# 4XKanda_1276_NoBME.net
KiCad netlist of a schematic drawn in EAGLE
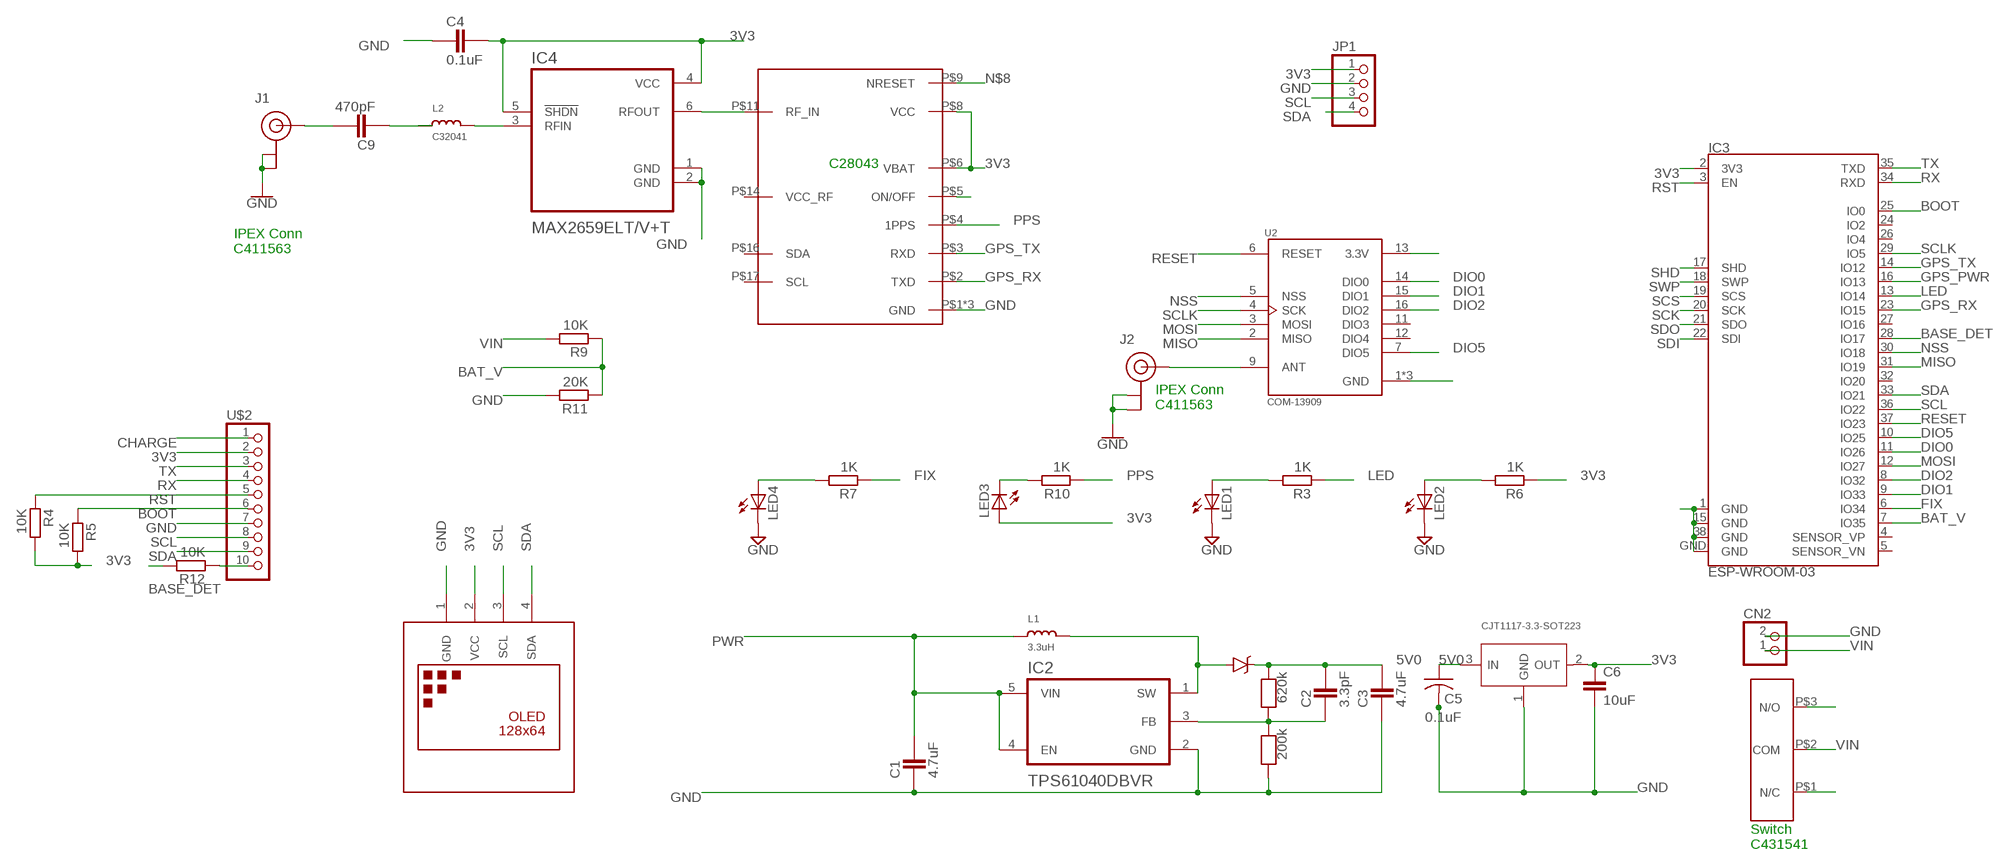
[diagram p0: schematic, sheet 1]
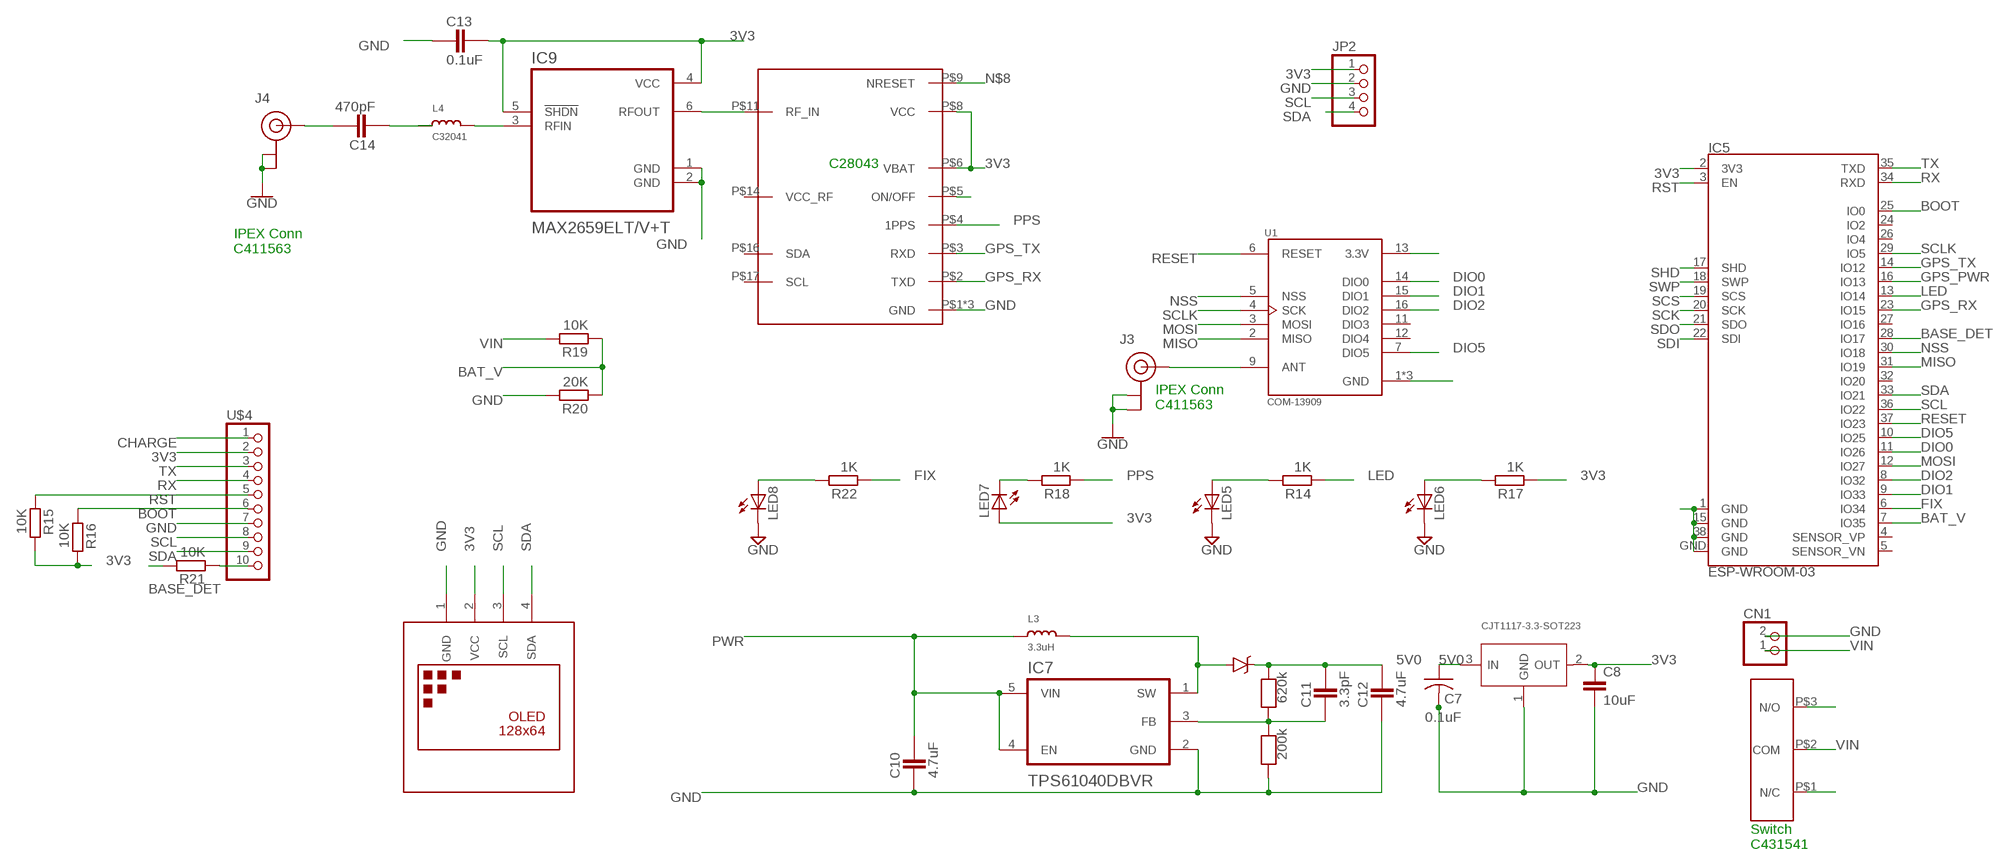
[diagram p1: schematic, sheet 2]
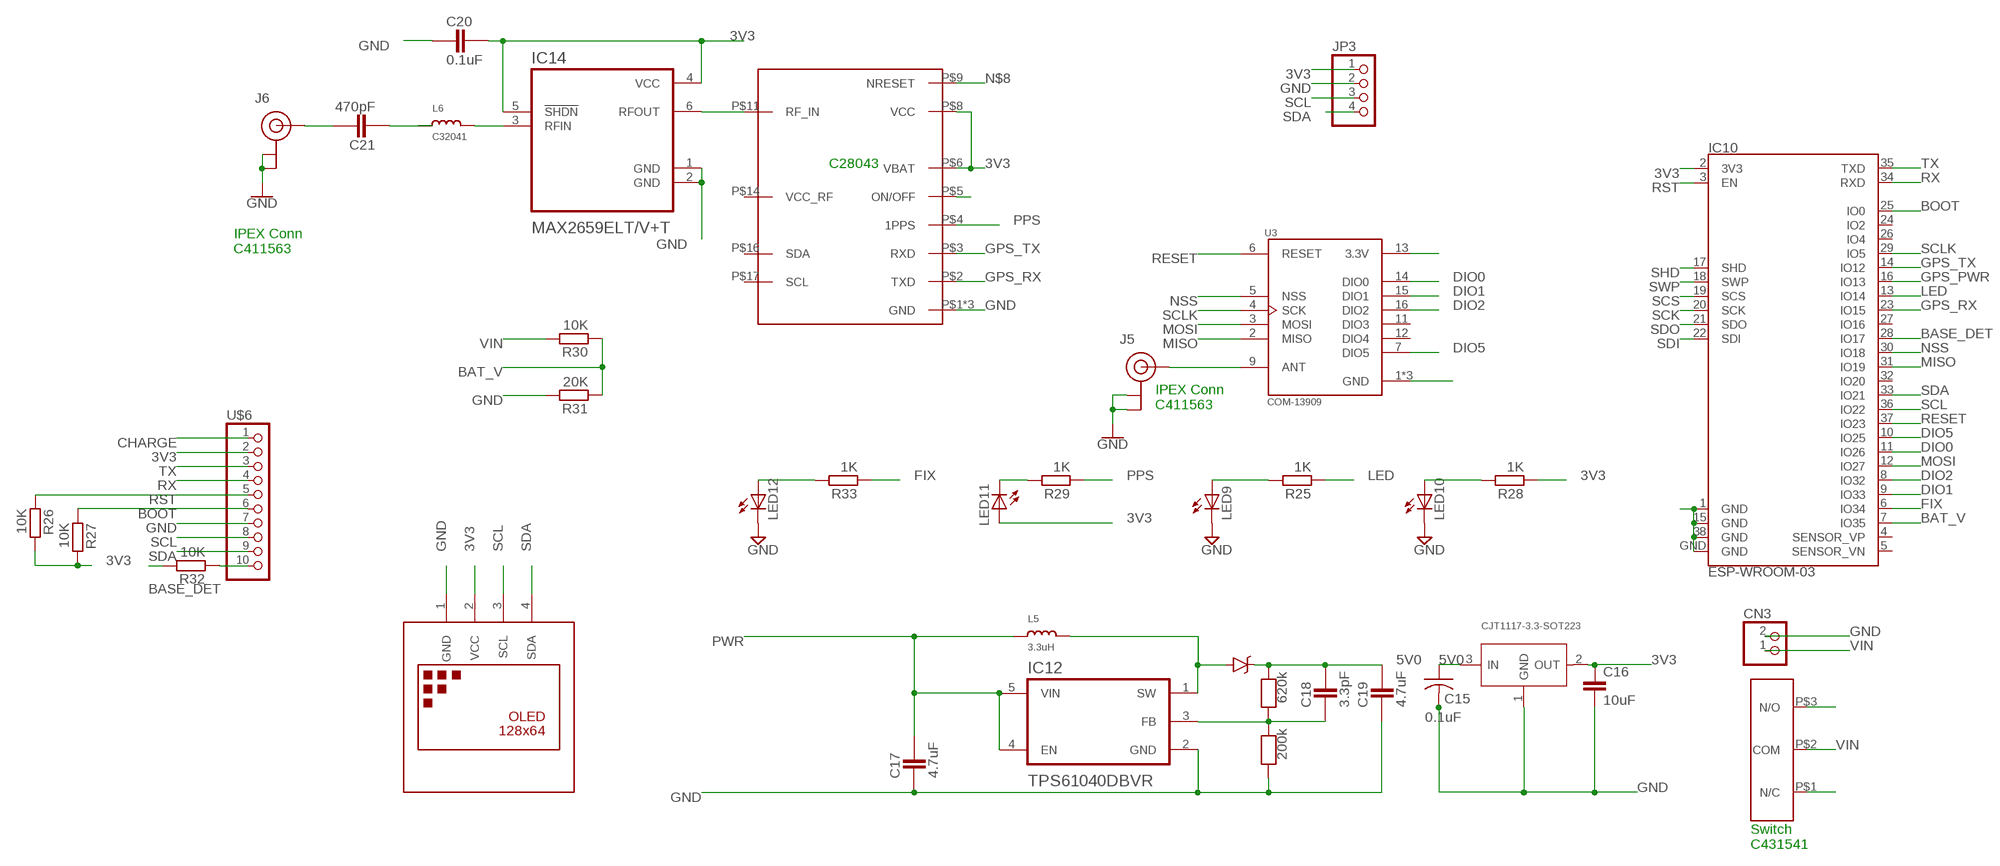
[diagram p2: schematic, sheet 3]
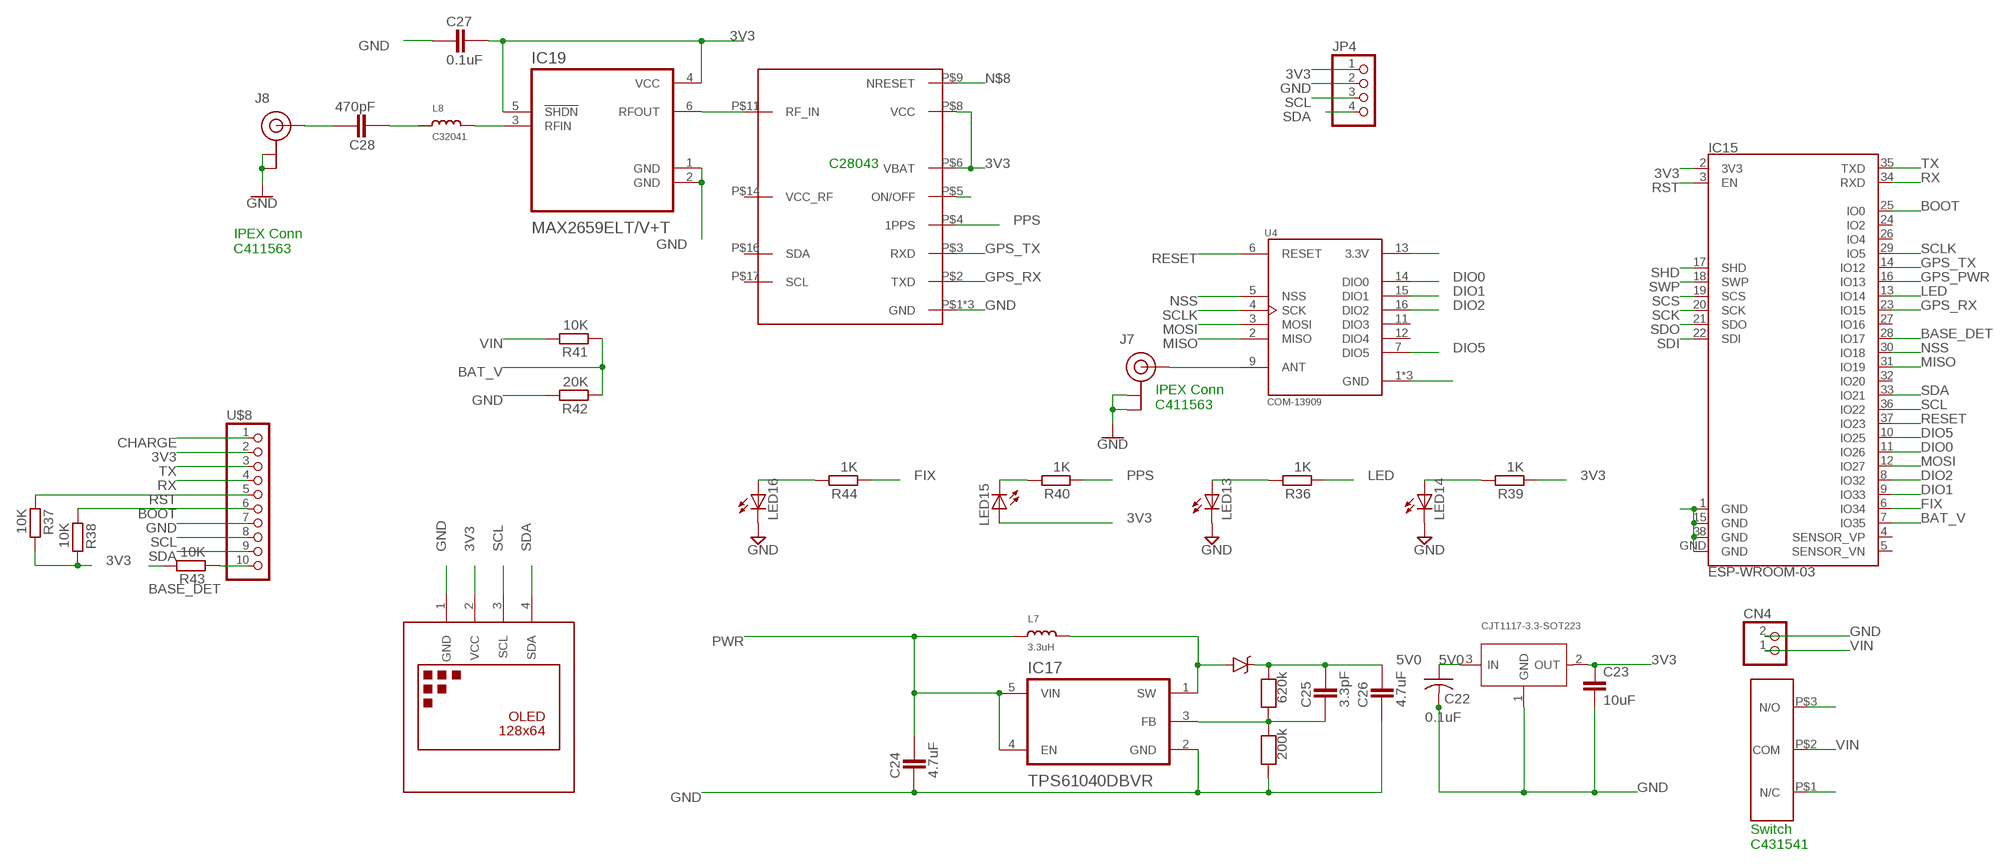
[diagram p3: schematic, sheet 4]

(export (version "E")
  (design (tool "Eeschema 10.0.6"))
  (components
    (comp (ref "C7")
      (value "0.1uF")
      (footprint "eagle-import:C0805")
      (libsource (lib "eagle-import") (part "C-USC0805"))
    )
    (comp (ref "C8")
      (value "10uF")
      (footprint "eagle-import:C0805@1")
      (libsource (lib "eagle-import") (part "C-EUC0805"))
    )
    (comp (ref "C10")
      (value "4.7uF")
      (footprint "eagle-import:CAPC1608X92N")
      (libsource (lib "eagle-import") (part "CAPACITOR_0603"))
    )
    (comp (ref "C11")
      (value "3.3pF")
      (footprint "eagle-import:CAPC1005X60N")
      (libsource (lib "eagle-import") (part "CAPACITOR_0402"))
    )
    (comp (ref "C12")
      (value "4.7uF")
      (footprint "eagle-import:CAPC1608X92N")
      (libsource (lib "eagle-import") (part "CAPACITOR_0603"))
    )
    (comp (ref "C13")
      (value "0.1uF")
      (footprint "eagle-import:CAPC1608X92N")
      (libsource (lib "eagle-import") (part "CAPACITOR_0603"))
    )
    (comp (ref "C14")
      (value "470pF")
      (footprint "eagle-import:CAPC1608X92N")
      (libsource (lib "eagle-import") (part "CAPACITOR_0603"))
    )
    (comp (ref "CN1")
      (value "JST_2PIN-THM")
      (footprint "eagle-import:JST-PH-2-THM")
      (libsource (lib "eagle-import") (part "JST_2PIN-THM"))
    )
    (comp (ref "D2")
      (value "BA340A")
      (footprint "eagle-import:SMA-DIODE")
      (libsource (lib "eagle-import") (part "B340A"))
    )
    (comp (ref "IC5")
      (value "ESP-WROOM-03")
      (footprint "eagle-import:ESP-WROOM-03")
      (libsource (lib "eagle-import") (part "ESP-WROOM-03"))
    )
    (comp (ref "IC6")
      (value "CJT1117-3.3-SOT223")
      (footprint "eagle-import:SOT-223")
      (fields (field (name "MPN") "CJT1117-3.3"))
      (libsource (lib "eagle-import") (part "PMIC-CJT1117-3.3(SOT223)"))
    )
    (comp (ref "IC7")
      (value "TPS61040DBVR")
      (footprint "eagle-import:SOT95P280X145-5N")
      (fields (field (name "MF") "Texas Instruments"))
      (libsource (lib "eagle-import") (part "TPS61040DBVR"))
    )
    (comp (ref "IC8")
      (value "ATGM336H")
      (footprint "eagle-import:ATGM336H")
      (libsource (lib "eagle-import") (part "ATGM336H"))
    )
    (comp (ref "IC9")
      (value "MAX2659ELT/V+T")
      (footprint "eagle-import:SON50P150X100X80-6N")
      (fields (field (name "MF") "Maxim Integrated") (field (name "MP") "MAX2659ELT/V+"))
      (libsource (lib "eagle-import") (part "MAX2659ELT/V+T"))
    )
    (comp (ref "J3")
      (value "U.FL")
      (footprint "eagle-import:U.FL")
      (libsource (lib "eagle-import") (part "U.FL"))
    )
    (comp (ref "J4")
      (value "U.FL")
      (footprint "eagle-import:U.FL")
      (libsource (lib "eagle-import") (part "U.FL"))
    )
    (comp (ref "JP2")
      (value "HEADER-1X4ROUND")
      (footprint "eagle-import:1X04_ROUND")
      (libsource (lib "eagle-import") (part "HEADER-1X4ROUND"))
    )
    (comp (ref "L3")
      (value "3.3uH")
      (footprint "eagle-import:INDUCTOR_5X5MM_NR5040_NOTHERMALS")
      (libsource (lib "eagle-import") (part "INDUCTORNR5040"))
    )
    (comp (ref "L4")
      (value "C32041")
      (footprint "eagle-import:_0402")
      (libsource (lib "eagle-import") (part "INDUCTOR_0402"))
    )
    (comp (ref "LED5")
      (value "LEDSML0805")
      (footprint "eagle-import:SML0805")
      (libsource (lib "eagle-import") (part "LEDSML0805"))
    )
    (comp (ref "LED6")
      (value "LEDSML0805")
      (footprint "eagle-import:SML0805")
      (libsource (lib "eagle-import") (part "LEDSML0805"))
    )
    (comp (ref "LED7")
      (value "LEDSML0805")
      (footprint "eagle-import:SML0805")
      (libsource (lib "eagle-import") (part "LEDSML0805"))
    )
    (comp (ref "LED8")
      (value "LEDSML0805")
      (footprint "eagle-import:SML0805")
      (libsource (lib "eagle-import") (part "LEDSML0805"))
    )
    (comp (ref "R8")
      (value "620k")
      (footprint "eagle-import:0603")
      (libsource (lib "eagle-import") (part "RESISTOR0603"))
    )
    (comp (ref "R13")
      (value "200k")
      (footprint "eagle-import:0603")
      (libsource (lib "eagle-import") (part "RESISTOR0603"))
    )
    (comp (ref "R14")
      (value "1K")
      (footprint "eagle-import:RESC1608X55N")
      (libsource (lib "eagle-import") (part "RESISTOR_0603"))
    )
    (comp (ref "R15")
      (value "10K")
      (footprint "eagle-import:RESC1608X55N")
      (libsource (lib "eagle-import") (part "RESISTOR_0603"))
    )
    (comp (ref "R16")
      (value "10K")
      (footprint "eagle-import:RESC1608X55N")
      (libsource (lib "eagle-import") (part "RESISTOR_0603"))
    )
    (comp (ref "R17")
      (value "1K")
      (footprint "eagle-import:RESC2012X70N")
      (libsource (lib "eagle-import") (part "RESISTOR_0805"))
    )
    (comp (ref "R18")
      (value "1K")
      (footprint "eagle-import:RESC1608X55N")
      (libsource (lib "eagle-import") (part "RESISTOR_0603"))
    )
    (comp (ref "R19")
      (value "10K")
      (footprint "eagle-import:RESC1608X55N")
      (libsource (lib "eagle-import") (part "RESISTOR_0603"))
    )
    (comp (ref "R20")
      (value "20K")
      (footprint "eagle-import:RESC1608X55N")
      (libsource (lib "eagle-import") (part "RESISTOR_0603"))
    )
    (comp (ref "R21")
      (value "10K")
      (footprint "eagle-import:RESC1608X55N")
      (libsource (lib "eagle-import") (part "RESISTOR_0603"))
    )
    (comp (ref "R22")
      (value "1K")
      (footprint "eagle-import:RESC1608X55N")
      (libsource (lib "eagle-import") (part "RESISTOR_0603"))
    )
    (comp (ref "S2")
      (value "SMD-SWITCH")
      (footprint "eagle-import:SMD-SWITCH")
      (libsource (lib "eagle-import") (part "SMD-SWITCH"))
    )
    (comp (ref "U$3")
      (value "DISPLAY-OLED-128X64-I2C")
      (footprint "eagle-import:DISPLAY-OLED-128X64-I2C")
      (libsource (lib "eagle-import") (part "DISPLAY-OLED-128X64-I2C"))
    )
    (comp (ref "U$4")
      (value "HEADER-1X10ROUND")
      (footprint "eagle-import:1X10_ROUND")
      (libsource (lib "eagle-import") (part "HEADER-1X10ROUND"))
    )
    (comp (ref "U1")
      (value "COM-13909")
      (footprint "eagle-import:MOD_COM-13909")
      (fields (field (name "MF") "HOPERF") (field (name "MP") "RFM69HCW-315S2"))
      (libsource (lib "eagle-import") (part "COM-13909"))
    )
    (comp (ref "C15")
      (value "0.1uF")
      (footprint "eagle-import:C0805")
      (libsource (lib "eagle-import") (part "C-USC0805"))
    )
    (comp (ref "C16")
      (value "10uF")
      (footprint "eagle-import:C0805@1")
      (libsource (lib "eagle-import") (part "C-EUC0805"))
    )
    (comp (ref "C17")
      (value "4.7uF")
      (footprint "eagle-import:CAPC1608X92N")
      (libsource (lib "eagle-import") (part "CAPACITOR_0603"))
    )
    (comp (ref "C18")
      (value "3.3pF")
      (footprint "eagle-import:CAPC1005X60N")
      (libsource (lib "eagle-import") (part "CAPACITOR_0402"))
    )
    (comp (ref "C19")
      (value "4.7uF")
      (footprint "eagle-import:CAPC1608X92N")
      (libsource (lib "eagle-import") (part "CAPACITOR_0603"))
    )
    (comp (ref "C20")
      (value "0.1uF")
      (footprint "eagle-import:CAPC1608X92N")
      (libsource (lib "eagle-import") (part "CAPACITOR_0603"))
    )
    (comp (ref "C21")
      (value "470pF")
      (footprint "eagle-import:CAPC1608X92N")
      (libsource (lib "eagle-import") (part "CAPACITOR_0603"))
    )
    (comp (ref "CN3")
      (value "JST_2PIN-THM")
      (footprint "eagle-import:JST-PH-2-THM")
      (libsource (lib "eagle-import") (part "JST_2PIN-THM"))
    )
    (comp (ref "D3")
      (value "BA340A")
      (footprint "eagle-import:SMA-DIODE")
      (libsource (lib "eagle-import") (part "B340A"))
    )
    (comp (ref "IC10")
      (value "ESP-WROOM-03")
      (footprint "eagle-import:ESP-WROOM-03")
      (libsource (lib "eagle-import") (part "ESP-WROOM-03"))
    )
    (comp (ref "IC11")
      (value "CJT1117-3.3-SOT223")
      (footprint "eagle-import:SOT-223")
      (fields (field (name "MPN") "CJT1117-3.3"))
      (libsource (lib "eagle-import") (part "PMIC-CJT1117-3.3(SOT223)"))
    )
    (comp (ref "IC12")
      (value "TPS61040DBVR")
      (footprint "eagle-import:SOT95P280X145-5N")
      (fields (field (name "MF") "Texas Instruments"))
      (libsource (lib "eagle-import") (part "TPS61040DBVR"))
    )
    (comp (ref "IC13")
      (value "ATGM336H")
      (footprint "eagle-import:ATGM336H")
      (libsource (lib "eagle-import") (part "ATGM336H"))
    )
    (comp (ref "IC14")
      (value "MAX2659ELT/V+T")
      (footprint "eagle-import:SON50P150X100X80-6N")
      (fields (field (name "MF") "Maxim Integrated") (field (name "MP") "MAX2659ELT/V+"))
      (libsource (lib "eagle-import") (part "MAX2659ELT/V+T"))
    )
    (comp (ref "J5")
      (value "U.FL")
      (footprint "eagle-import:U.FL")
      (libsource (lib "eagle-import") (part "U.FL"))
    )
    (comp (ref "J6")
      (value "U.FL")
      (footprint "eagle-import:U.FL")
      (libsource (lib "eagle-import") (part "U.FL"))
    )
    (comp (ref "JP3")
      (value "HEADER-1X4ROUND")
      (footprint "eagle-import:1X04_ROUND")
      (libsource (lib "eagle-import") (part "HEADER-1X4ROUND"))
    )
    (comp (ref "L5")
      (value "3.3uH")
      (footprint "eagle-import:INDUCTOR_5X5MM_NR5040_NOTHERMALS")
      (libsource (lib "eagle-import") (part "INDUCTORNR5040"))
    )
    (comp (ref "L6")
      (value "C32041")
      (footprint "eagle-import:_0402")
      (libsource (lib "eagle-import") (part "INDUCTOR_0402"))
    )
    (comp (ref "LED9")
      (value "LEDSML0805")
      (footprint "eagle-import:SML0805")
      (libsource (lib "eagle-import") (part "LEDSML0805"))
    )
    (comp (ref "LED10")
      (value "LEDSML0805")
      (footprint "eagle-import:SML0805")
      (libsource (lib "eagle-import") (part "LEDSML0805"))
    )
    (comp (ref "LED11")
      (value "LEDSML0805")
      (footprint "eagle-import:SML0805")
      (libsource (lib "eagle-import") (part "LEDSML0805"))
    )
    (comp (ref "LED12")
      (value "LEDSML0805")
      (footprint "eagle-import:SML0805")
      (libsource (lib "eagle-import") (part "LEDSML0805"))
    )
    (comp (ref "R23")
      (value "620k")
      (footprint "eagle-import:0603")
      (libsource (lib "eagle-import") (part "RESISTOR0603"))
    )
    (comp (ref "R24")
      (value "200k")
      (footprint "eagle-import:0603")
      (libsource (lib "eagle-import") (part "RESISTOR0603"))
    )
    (comp (ref "R25")
      (value "1K")
      (footprint "eagle-import:RESC1608X55N")
      (libsource (lib "eagle-import") (part "RESISTOR_0603"))
    )
    (comp (ref "R26")
      (value "10K")
      (footprint "eagle-import:RESC1608X55N")
      (libsource (lib "eagle-import") (part "RESISTOR_0603"))
    )
    (comp (ref "R27")
      (value "10K")
      (footprint "eagle-import:RESC1608X55N")
      (libsource (lib "eagle-import") (part "RESISTOR_0603"))
    )
    (comp (ref "R28")
      (value "1K")
      (footprint "eagle-import:RESC2012X70N")
      (libsource (lib "eagle-import") (part "RESISTOR_0805"))
    )
    (comp (ref "R29")
      (value "1K")
      (footprint "eagle-import:RESC1608X55N")
      (libsource (lib "eagle-import") (part "RESISTOR_0603"))
    )
    (comp (ref "R30")
      (value "10K")
      (footprint "eagle-import:RESC1608X55N")
      (libsource (lib "eagle-import") (part "RESISTOR_0603"))
    )
    (comp (ref "R31")
      (value "20K")
      (footprint "eagle-import:RESC1608X55N")
      (libsource (lib "eagle-import") (part "RESISTOR_0603"))
    )
    (comp (ref "R32")
      (value "10K")
      (footprint "eagle-import:RESC1608X55N")
      (libsource (lib "eagle-import") (part "RESISTOR_0603"))
    )
    (comp (ref "R33")
      (value "1K")
      (footprint "eagle-import:RESC1608X55N")
      (libsource (lib "eagle-import") (part "RESISTOR_0603"))
    )
    (comp (ref "S3")
      (value "SMD-SWITCH")
      (footprint "eagle-import:SMD-SWITCH")
      (libsource (lib "eagle-import") (part "SMD-SWITCH"))
    )
    (comp (ref "U$5")
      (value "DISPLAY-OLED-128X64-I2C")
      (footprint "eagle-import:DISPLAY-OLED-128X64-I2C")
      (libsource (lib "eagle-import") (part "DISPLAY-OLED-128X64-I2C"))
    )
    (comp (ref "U$6")
      (value "HEADER-1X10ROUND")
      (footprint "eagle-import:1X10_ROUND")
      (libsource (lib "eagle-import") (part "HEADER-1X10ROUND"))
    )
    (comp (ref "U3")
      (value "COM-13909")
      (footprint "eagle-import:MOD_COM-13909")
      (fields (field (name "MF") "HOPERF") (field (name "MP") "RFM69HCW-315S2"))
      (libsource (lib "eagle-import") (part "COM-13909"))
    )
    (comp (ref "C22")
      (value "0.1uF")
      (footprint "eagle-import:C0805")
      (libsource (lib "eagle-import") (part "C-USC0805"))
    )
    (comp (ref "C23")
      (value "10uF")
      (footprint "eagle-import:C0805@1")
      (libsource (lib "eagle-import") (part "C-EUC0805"))
    )
    (comp (ref "C24")
      (value "4.7uF")
      (footprint "eagle-import:CAPC1608X92N")
      (libsource (lib "eagle-import") (part "CAPACITOR_0603"))
    )
    (comp (ref "C25")
      (value "3.3pF")
      (footprint "eagle-import:CAPC1005X60N")
      (libsource (lib "eagle-import") (part "CAPACITOR_0402"))
    )
    (comp (ref "C26")
      (value "4.7uF")
      (footprint "eagle-import:CAPC1608X92N")
      (libsource (lib "eagle-import") (part "CAPACITOR_0603"))
    )
    (comp (ref "C27")
      (value "0.1uF")
      (footprint "eagle-import:CAPC1608X92N")
      (libsource (lib "eagle-import") (part "CAPACITOR_0603"))
    )
    (comp (ref "C28")
      (value "470pF")
      (footprint "eagle-import:CAPC1608X92N")
      (libsource (lib "eagle-import") (part "CAPACITOR_0603"))
    )
    (comp (ref "CN4")
      (value "JST_2PIN-THM")
      (footprint "eagle-import:JST-PH-2-THM")
      (libsource (lib "eagle-import") (part "JST_2PIN-THM"))
    )
    (comp (ref "D4")
      (value "BA340A")
      (footprint "eagle-import:SMA-DIODE")
      (libsource (lib "eagle-import") (part "B340A"))
    )
    (comp (ref "IC15")
      (value "ESP-WROOM-03")
      (footprint "eagle-import:ESP-WROOM-03")
      (libsource (lib "eagle-import") (part "ESP-WROOM-03"))
    )
    (comp (ref "IC16")
      (value "CJT1117-3.3-SOT223")
      (footprint "eagle-import:SOT-223")
      (fields (field (name "MPN") "CJT1117-3.3"))
      (libsource (lib "eagle-import") (part "PMIC-CJT1117-3.3(SOT223)"))
    )
    (comp (ref "IC17")
      (value "TPS61040DBVR")
      (footprint "eagle-import:SOT95P280X145-5N")
      (fields (field (name "MF") "Texas Instruments"))
      (libsource (lib "eagle-import") (part "TPS61040DBVR"))
    )
    (comp (ref "IC18")
      (value "ATGM336H")
      (footprint "eagle-import:ATGM336H")
      (libsource (lib "eagle-import") (part "ATGM336H"))
    )
    (comp (ref "IC19")
      (value "MAX2659ELT/V+T")
      (footprint "eagle-import:SON50P150X100X80-6N")
      (fields (field (name "MF") "Maxim Integrated") (field (name "MP") "MAX2659ELT/V+"))
      (libsource (lib "eagle-import") (part "MAX2659ELT/V+T"))
    )
    (comp (ref "J7")
      (value "U.FL")
      (footprint "eagle-import:U.FL")
      (libsource (lib "eagle-import") (part "U.FL"))
    )
    (comp (ref "J8")
      (value "U.FL")
      (footprint "eagle-import:U.FL")
      (libsource (lib "eagle-import") (part "U.FL"))
    )
    (comp (ref "JP4")
      (value "HEADER-1X4ROUND")
      (footprint "eagle-import:1X04_ROUND")
      (libsource (lib "eagle-import") (part "HEADER-1X4ROUND"))
    )
    (comp (ref "L7")
      (value "3.3uH")
      (footprint "eagle-import:INDUCTOR_5X5MM_NR5040_NOTHERMALS")
      (libsource (lib "eagle-import") (part "INDUCTORNR5040"))
    )
    (comp (ref "L8")
      (value "C32041")
      (footprint "eagle-import:_0402")
      (libsource (lib "eagle-import") (part "INDUCTOR_0402"))
    )
    (comp (ref "LED13")
      (value "LEDSML0805")
      (footprint "eagle-import:SML0805")
      (libsource (lib "eagle-import") (part "LEDSML0805"))
    )
    (comp (ref "LED14")
      (value "LEDSML0805")
      (footprint "eagle-import:SML0805")
      (libsource (lib "eagle-import") (part "LEDSML0805"))
    )
    (comp (ref "LED15")
      (value "LEDSML0805")
      (footprint "eagle-import:SML0805")
      (libsource (lib "eagle-import") (part "LEDSML0805"))
    )
    (comp (ref "LED16")
      (value "LEDSML0805")
      (footprint "eagle-import:SML0805")
      (libsource (lib "eagle-import") (part "LEDSML0805"))
    )
    (comp (ref "R34")
      (value "620k")
      (footprint "eagle-import:0603")
      (libsource (lib "eagle-import") (part "RESISTOR0603"))
    )
    (comp (ref "R35")
      (value "200k")
      (footprint "eagle-import:0603")
      (libsource (lib "eagle-import") (part "RESISTOR0603"))
    )
    (comp (ref "R36")
      (value "1K")
      (footprint "eagle-import:RESC1608X55N")
      (libsource (lib "eagle-import") (part "RESISTOR_0603"))
    )
    (comp (ref "R37")
      (value "10K")
      (footprint "eagle-import:RESC1608X55N")
      (libsource (lib "eagle-import") (part "RESISTOR_0603"))
    )
    (comp (ref "R38")
      (value "10K")
      (footprint "eagle-import:RESC1608X55N")
      (libsource (lib "eagle-import") (part "RESISTOR_0603"))
    )
    (comp (ref "R39")
      (value "1K")
      (footprint "eagle-import:RESC2012X70N")
      (libsource (lib "eagle-import") (part "RESISTOR_0805"))
    )
    (comp (ref "R40")
      (value "1K")
      (footprint "eagle-import:RESC1608X55N")
      (libsource (lib "eagle-import") (part "RESISTOR_0603"))
    )
    (comp (ref "R41")
      (value "10K")
      (footprint "eagle-import:RESC1608X55N")
      (libsource (lib "eagle-import") (part "RESISTOR_0603"))
    )
    (comp (ref "R42")
      (value "20K")
      (footprint "eagle-import:RESC1608X55N")
      (libsource (lib "eagle-import") (part "RESISTOR_0603"))
    )
    (comp (ref "R43")
      (value "10K")
      (footprint "eagle-import:RESC1608X55N")
      (libsource (lib "eagle-import") (part "RESISTOR_0603"))
    )
    (comp (ref "R44")
      (value "1K")
      (footprint "eagle-import:RESC1608X55N")
      (libsource (lib "eagle-import") (part "RESISTOR_0603"))
    )
    (comp (ref "S4")
      (value "SMD-SWITCH")
      (footprint "eagle-import:SMD-SWITCH")
      (libsource (lib "eagle-import") (part "SMD-SWITCH"))
    )
    (comp (ref "U$7")
      (value "DISPLAY-OLED-128X64-I2C")
      (footprint "eagle-import:DISPLAY-OLED-128X64-I2C")
      (libsource (lib "eagle-import") (part "DISPLAY-OLED-128X64-I2C"))
    )
    (comp (ref "U$8")
      (value "HEADER-1X10ROUND")
      (footprint "eagle-import:1X10_ROUND")
      (libsource (lib "eagle-import") (part "HEADER-1X10ROUND"))
    )
    (comp (ref "U4")
      (value "COM-13909")
      (footprint "eagle-import:MOD_COM-13909")
      (fields (field (name "MF") "HOPERF") (field (name "MP") "RFM69HCW-315S2"))
      (libsource (lib "eagle-import") (part "COM-13909"))
    )
    (comp (ref "C1")
      (value "4.7uF")
      (footprint "eagle-import:CAPC1608X92N")
      (libsource (lib "eagle-import") (part "CAPACITOR_0603"))
    )
    (comp (ref "C2")
      (value "3.3pF")
      (footprint "eagle-import:CAPC1005X60N")
      (libsource (lib "eagle-import") (part "CAPACITOR_0402"))
    )
    (comp (ref "C3")
      (value "4.7uF")
      (footprint "eagle-import:CAPC1608X92N")
      (libsource (lib "eagle-import") (part "CAPACITOR_0603"))
    )
    (comp (ref "C4")
      (value "0.1uF")
      (footprint "eagle-import:CAPC1608X92N")
      (libsource (lib "eagle-import") (part "CAPACITOR_0603"))
    )
    (comp (ref "C5")
      (value "0.1uF")
      (footprint "eagle-import:C0805")
      (libsource (lib "eagle-import") (part "C-USC0805"))
    )
    (comp (ref "C6")
      (value "10uF")
      (footprint "eagle-import:C0805@1")
      (libsource (lib "eagle-import") (part "C-EUC0805"))
    )
    (comp (ref "C9")
      (value "470pF")
      (footprint "eagle-import:CAPC1608X92N")
      (libsource (lib "eagle-import") (part "CAPACITOR_0603"))
    )
    (comp (ref "CN2")
      (value "JST_2PIN-THM")
      (footprint "eagle-import:JST-PH-2-THM")
      (libsource (lib "eagle-import") (part "JST_2PIN-THM"))
    )
    (comp (ref "D1")
      (value "BA340A")
      (footprint "eagle-import:SMA-DIODE")
      (libsource (lib "eagle-import") (part "B340A"))
    )
    (comp (ref "IC1")
      (value "CJT1117-3.3-SOT223")
      (footprint "eagle-import:SOT-223")
      (fields (field (name "MPN") "CJT1117-3.3"))
      (libsource (lib "eagle-import") (part "PMIC-CJT1117-3.3(SOT223)"))
    )
    (comp (ref "IC2")
      (value "TPS61040DBVR")
      (footprint "eagle-import:SOT95P280X145-5N")
      (fields (field (name "MF") "Texas Instruments"))
      (libsource (lib "eagle-import") (part "TPS61040DBVR"))
    )
    (comp (ref "IC3")
      (value "ESP-WROOM-03")
      (footprint "eagle-import:ESP-WROOM-03")
      (libsource (lib "eagle-import") (part "ESP-WROOM-03"))
    )
    (comp (ref "IC4")
      (value "MAX2659ELT/V+T")
      (footprint "eagle-import:SON50P150X100X80-6N")
      (fields (field (name "MF") "Maxim Integrated") (field (name "MP") "MAX2659ELT/V+"))
      (libsource (lib "eagle-import") (part "MAX2659ELT/V+T"))
    )
    (comp (ref "IC54")
      (value "ATGM336H")
      (footprint "eagle-import:ATGM336H")
      (libsource (lib "eagle-import") (part "ATGM336H"))
    )
    (comp (ref "J1")
      (value "U.FL")
      (footprint "eagle-import:U.FL")
      (libsource (lib "eagle-import") (part "U.FL"))
    )
    (comp (ref "J2")
      (value "U.FL")
      (footprint "eagle-import:U.FL")
      (libsource (lib "eagle-import") (part "U.FL"))
    )
    (comp (ref "JP1")
      (value "HEADER-1X4ROUND")
      (footprint "eagle-import:1X04_ROUND")
      (libsource (lib "eagle-import") (part "HEADER-1X4ROUND"))
    )
    (comp (ref "L1")
      (value "3.3uH")
      (footprint "eagle-import:INDUCTOR_5X5MM_NR5040_NOTHERMALS")
      (libsource (lib "eagle-import") (part "INDUCTORNR5040"))
    )
    (comp (ref "L2")
      (value "C32041")
      (footprint "eagle-import:_0402")
      (libsource (lib "eagle-import") (part "INDUCTOR_0402"))
    )
    (comp (ref "LED1")
      (value "LEDSML0805")
      (footprint "eagle-import:SML0805")
      (libsource (lib "eagle-import") (part "LEDSML0805"))
    )
    (comp (ref "LED2")
      (value "LEDSML0805")
      (footprint "eagle-import:SML0805")
      (libsource (lib "eagle-import") (part "LEDSML0805"))
    )
    (comp (ref "LED3")
      (value "LEDSML0805")
      (footprint "eagle-import:SML0805")
      (libsource (lib "eagle-import") (part "LEDSML0805"))
    )
    (comp (ref "LED4")
      (value "LEDSML0805")
      (footprint "eagle-import:SML0805")
      (libsource (lib "eagle-import") (part "LEDSML0805"))
    )
    (comp (ref "R1")
      (value "620k")
      (footprint "eagle-import:0603")
      (libsource (lib "eagle-import") (part "RESISTOR0603"))
    )
    (comp (ref "R2")
      (value "200k")
      (footprint "eagle-import:0603")
      (libsource (lib "eagle-import") (part "RESISTOR0603"))
    )
    (comp (ref "R3")
      (value "1K")
      (footprint "eagle-import:RESC1608X55N")
      (libsource (lib "eagle-import") (part "RESISTOR_0603"))
    )
    (comp (ref "R4")
      (value "10K")
      (footprint "eagle-import:RESC1608X55N")
      (libsource (lib "eagle-import") (part "RESISTOR_0603"))
    )
    (comp (ref "R5")
      (value "10K")
      (footprint "eagle-import:RESC1608X55N")
      (libsource (lib "eagle-import") (part "RESISTOR_0603"))
    )
    (comp (ref "R6")
      (value "1K")
      (footprint "eagle-import:RESC2012X70N")
      (libsource (lib "eagle-import") (part "RESISTOR_0805"))
    )
    (comp (ref "R7")
      (value "1K")
      (footprint "eagle-import:RESC1608X55N")
      (libsource (lib "eagle-import") (part "RESISTOR_0603"))
    )
    (comp (ref "R9")
      (value "10K")
      (footprint "eagle-import:RESC1608X55N")
      (libsource (lib "eagle-import") (part "RESISTOR_0603"))
    )
    (comp (ref "R10")
      (value "1K")
      (footprint "eagle-import:RESC1608X55N")
      (libsource (lib "eagle-import") (part "RESISTOR_0603"))
    )
    (comp (ref "R11")
      (value "20K")
      (footprint "eagle-import:RESC1608X55N")
      (libsource (lib "eagle-import") (part "RESISTOR_0603"))
    )
    (comp (ref "R12")
      (value "10K")
      (footprint "eagle-import:RESC1608X55N")
      (libsource (lib "eagle-import") (part "RESISTOR_0603"))
    )
    (comp (ref "S1")
      (value "SMD-SWITCH")
      (footprint "eagle-import:SMD-SWITCH")
      (libsource (lib "eagle-import") (part "SMD-SWITCH"))
    )
    (comp (ref "U$1")
      (value "DISPLAY-OLED-128X64-I2C")
      (footprint "eagle-import:DISPLAY-OLED-128X64-I2C")
      (libsource (lib "eagle-import") (part "DISPLAY-OLED-128X64-I2C"))
    )
    (comp (ref "U$2")
      (value "HEADER-1X10ROUND")
      (footprint "eagle-import:1X10_ROUND")
      (libsource (lib "eagle-import") (part "HEADER-1X10ROUND"))
    )
    (comp (ref "U2")
      (value "COM-13909")
      (footprint "eagle-import:MOD_COM-13909")
      (fields (field (name "MF") "HOPERF") (field (name "MP") "RFM69HCW-315S2"))
      (libsource (lib "eagle-import") (part "COM-13909"))
    )
  )
  (nets
    (net (code "1") (name "3V3") (class "Default")
      (node (ref "C13") (pin "2") (pinfunction "2_2") (pintype "passive"))
      (node (ref "C16") (pin "1") (pinfunction "1_1") (pintype "passive"))
      (node (ref "C20") (pin "2") (pinfunction "2_2") (pintype "passive"))
      (node (ref "C23") (pin "1") (pinfunction "1_1") (pintype "passive"))
      (node (ref "C27") (pin "2") (pinfunction "2_2") (pintype "passive"))
      (node (ref "C4") (pin "2") (pinfunction "2_2") (pintype "passive"))
      (node (ref "C6") (pin "1") (pinfunction "1_1") (pintype "passive"))
      (node (ref "C8") (pin "1") (pinfunction "1_1") (pintype "passive"))
      (node (ref "IC1") (pin "2") (pinfunction "OUT_2") (pintype "bidirectional"))
      (node (ref "IC10") (pin "2") (pinfunction "3V3_2") (pintype "bidirectional"))
      (node (ref "IC11") (pin "2") (pinfunction "OUT_2") (pintype "bidirectional"))
      (node (ref "IC13") (pin "P$6") (pinfunction "VBAT_P$6") (pintype "bidirectional"))
      (node (ref "IC13") (pin "P$8") (pinfunction "VCC_P$8") (pintype "bidirectional"))
      (node (ref "IC14") (pin "4") (pinfunction "VCC_4") (pintype "power_in"))
      (node (ref "IC14") (pin "5") (pinfunction "~{SHDN}_5") (pintype "input"))
      (node (ref "IC15") (pin "2") (pinfunction "3V3_2") (pintype "bidirectional"))
      (node (ref "IC16") (pin "2") (pinfunction "OUT_2") (pintype "bidirectional"))
      (node (ref "IC18") (pin "P$6") (pinfunction "VBAT_P$6") (pintype "bidirectional"))
      (node (ref "IC18") (pin "P$8") (pinfunction "VCC_P$8") (pintype "bidirectional"))
      (node (ref "IC19") (pin "4") (pinfunction "VCC_4") (pintype "power_in"))
      (node (ref "IC19") (pin "5") (pinfunction "~{SHDN}_5") (pintype "input"))
      (node (ref "IC3") (pin "2") (pinfunction "3V3_2") (pintype "bidirectional"))
      (node (ref "IC4") (pin "4") (pinfunction "VCC_4") (pintype "power_in"))
      (node (ref "IC4") (pin "5") (pinfunction "~{SHDN}_5") (pintype "input"))
      (node (ref "IC5") (pin "2") (pinfunction "3V3_2") (pintype "bidirectional"))
      (node (ref "IC54") (pin "P$6") (pinfunction "VBAT_P$6") (pintype "bidirectional"))
      (node (ref "IC54") (pin "P$8") (pinfunction "VCC_P$8") (pintype "bidirectional"))
      (node (ref "IC6") (pin "2") (pinfunction "OUT_2") (pintype "bidirectional"))
      (node (ref "IC8") (pin "P$6") (pinfunction "VBAT_P$6") (pintype "bidirectional"))
      (node (ref "IC8") (pin "P$8") (pinfunction "VCC_P$8") (pintype "bidirectional"))
      (node (ref "IC9") (pin "4") (pinfunction "VCC_4") (pintype "power_in"))
      (node (ref "IC9") (pin "5") (pinfunction "~{SHDN}_5") (pintype "input"))
      (node (ref "JP1") (pin "1") (pinfunction "1_1") (pintype "passive"))
      (node (ref "JP2") (pin "1") (pinfunction "1_1") (pintype "passive"))
      (node (ref "JP3") (pin "1") (pinfunction "1_1") (pintype "passive"))
      (node (ref "JP4") (pin "1") (pinfunction "1_1") (pintype "passive"))
      (node (ref "LED11") (pin "A") (pinfunction "A_A") (pintype "passive"))
      (node (ref "LED15") (pin "A") (pinfunction "A_A") (pintype "passive"))
      (node (ref "LED3") (pin "A") (pinfunction "A_A") (pintype "passive"))
      (node (ref "LED7") (pin "A") (pinfunction "A_A") (pintype "passive"))
      (node (ref "R15") (pin "2") (pinfunction "2_2") (pintype "passive"))
      (node (ref "R16") (pin "2") (pinfunction "2_2") (pintype "passive"))
      (node (ref "R17") (pin "1") (pinfunction "1_1") (pintype "passive"))
      (node (ref "R26") (pin "2") (pinfunction "2_2") (pintype "passive"))
      (node (ref "R27") (pin "2") (pinfunction "2_2") (pintype "passive"))
      (node (ref "R28") (pin "1") (pinfunction "1_1") (pintype "passive"))
      (node (ref "R37") (pin "2") (pinfunction "2_2") (pintype "passive"))
      (node (ref "R38") (pin "2") (pinfunction "2_2") (pintype "passive"))
      (node (ref "R39") (pin "1") (pinfunction "1_1") (pintype "passive"))
      (node (ref "R4") (pin "2") (pinfunction "2_2") (pintype "passive"))
      (node (ref "R5") (pin "2") (pinfunction "2_2") (pintype "passive"))
      (node (ref "R6") (pin "1") (pinfunction "1_1") (pintype "passive"))
      (node (ref "U$1") (pin "2") (pinfunction "VCC_2") (pintype "power_in"))
      (node (ref "U$2") (pin "2") (pinfunction "2_2") (pintype "passive"))
      (node (ref "U$3") (pin "2") (pinfunction "VCC_2") (pintype "power_in"))
      (node (ref "U$4") (pin "2") (pinfunction "2_2") (pintype "passive"))
      (node (ref "U$5") (pin "2") (pinfunction "VCC_2") (pintype "power_in"))
      (node (ref "U$6") (pin "2") (pinfunction "2_2") (pintype "passive"))
      (node (ref "U$7") (pin "2") (pinfunction "VCC_2") (pintype "power_in"))
      (node (ref "U$8") (pin "2") (pinfunction "2_2") (pintype "passive"))
      (node (ref "U1") (pin "13") (pinfunction "3.3V_13") (pintype "power_in"))
      (node (ref "U2") (pin "13") (pinfunction "3.3V_13") (pintype "power_in"))
      (node (ref "U3") (pin "13") (pinfunction "3.3V_13") (pintype "power_in"))
      (node (ref "U4") (pin "13") (pinfunction "3.3V_13") (pintype "power_in"))
    )
    (net (code "2") (name "5V0") (class "Default")
      (node (ref "C11") (pin "2") (pinfunction "2_2") (pintype "passive"))
      (node (ref "C12") (pin "2") (pinfunction "2_2") (pintype "passive"))
      (node (ref "C15") (pin "1") (pinfunction "1_1") (pintype "passive"))
      (node (ref "C18") (pin "2") (pinfunction "2_2") (pintype "passive"))
      (node (ref "C19") (pin "2") (pinfunction "2_2") (pintype "passive"))
      (node (ref "C2") (pin "2") (pinfunction "2_2") (pintype "passive"))
      (node (ref "C22") (pin "1") (pinfunction "1_1") (pintype "passive"))
      (node (ref "C25") (pin "2") (pinfunction "2_2") (pintype "passive"))
      (node (ref "C26") (pin "2") (pinfunction "2_2") (pintype "passive"))
      (node (ref "C3") (pin "2") (pinfunction "2_2") (pintype "passive"))
      (node (ref "C5") (pin "1") (pinfunction "1_1") (pintype "passive"))
      (node (ref "C7") (pin "1") (pinfunction "1_1") (pintype "passive"))
      (node (ref "D1") (pin "C") (pinfunction "C_C") (pintype "passive"))
      (node (ref "D2") (pin "C") (pinfunction "C_C") (pintype "passive"))
      (node (ref "D3") (pin "C") (pinfunction "C_C") (pintype "passive"))
      (node (ref "D4") (pin "C") (pinfunction "C_C") (pintype "passive"))
      (node (ref "IC1") (pin "3") (pinfunction "IN_3") (pintype "bidirectional"))
      (node (ref "IC11") (pin "3") (pinfunction "IN_3") (pintype "bidirectional"))
      (node (ref "IC16") (pin "3") (pinfunction "IN_3") (pintype "bidirectional"))
      (node (ref "IC6") (pin "3") (pinfunction "IN_3") (pintype "bidirectional"))
      (node (ref "R1") (pin "1") (pinfunction "1_1") (pintype "passive"))
      (node (ref "R23") (pin "1") (pinfunction "1_1") (pintype "passive"))
      (node (ref "R34") (pin "1") (pinfunction "1_1") (pintype "passive"))
      (node (ref "R8") (pin "1") (pinfunction "1_1") (pintype "passive"))
    )
    (net (code "3") (name "BASE_DET") (class "Default")
      (node (ref "IC10") (pin "28") (pinfunction "IO17_28") (pintype "bidirectional"))
      (node (ref "IC15") (pin "28") (pinfunction "IO17_28") (pintype "bidirectional"))
      (node (ref "IC3") (pin "28") (pinfunction "IO17_28") (pintype "bidirectional"))
      (node (ref "IC5") (pin "28") (pinfunction "IO17_28") (pintype "bidirectional"))
      (node (ref "R12") (pin "2") (pinfunction "2_2") (pintype "passive"))
      (node (ref "R21") (pin "2") (pinfunction "2_2") (pintype "passive"))
      (node (ref "R32") (pin "2") (pinfunction "2_2") (pintype "passive"))
      (node (ref "R43") (pin "2") (pinfunction "2_2") (pintype "passive"))
    )
    (net (code "4") (name "BAT_V") (class "Default")
      (node (ref "IC10") (pin "7") (pinfunction "IO35_7") (pintype "bidirectional"))
      (node (ref "IC15") (pin "7") (pinfunction "IO35_7") (pintype "bidirectional"))
      (node (ref "IC3") (pin "7") (pinfunction "IO35_7") (pintype "bidirectional"))
      (node (ref "IC5") (pin "7") (pinfunction "IO35_7") (pintype "bidirectional"))
      (node (ref "R11") (pin "1") (pinfunction "1_1") (pintype "passive"))
      (node (ref "R19") (pin "1") (pinfunction "1_1") (pintype "passive"))
      (node (ref "R20") (pin "1") (pinfunction "1_1") (pintype "passive"))
      (node (ref "R30") (pin "1") (pinfunction "1_1") (pintype "passive"))
      (node (ref "R31") (pin "1") (pinfunction "1_1") (pintype "passive"))
      (node (ref "R41") (pin "1") (pinfunction "1_1") (pintype "passive"))
      (node (ref "R42") (pin "1") (pinfunction "1_1") (pintype "passive"))
      (node (ref "R9") (pin "1") (pinfunction "1_1") (pintype "passive"))
    )
    (net (code "5") (name "BOOT") (class "Default")
      (node (ref "IC10") (pin "25") (pinfunction "IO0_25") (pintype "bidirectional"))
      (node (ref "IC15") (pin "25") (pinfunction "IO0_25") (pintype "bidirectional"))
      (node (ref "IC3") (pin "25") (pinfunction "IO0_25") (pintype "bidirectional"))
      (node (ref "IC5") (pin "25") (pinfunction "IO0_25") (pintype "bidirectional"))
      (node (ref "R16") (pin "1") (pinfunction "1_1") (pintype "passive"))
      (node (ref "R27") (pin "1") (pinfunction "1_1") (pintype "passive"))
      (node (ref "R38") (pin "1") (pinfunction "1_1") (pintype "passive"))
      (node (ref "R5") (pin "1") (pinfunction "1_1") (pintype "passive"))
      (node (ref "U$2") (pin "6") (pinfunction "6_6") (pintype "passive"))
      (node (ref "U$4") (pin "6") (pinfunction "6_6") (pintype "passive"))
      (node (ref "U$6") (pin "6") (pinfunction "6_6") (pintype "passive"))
      (node (ref "U$8") (pin "6") (pinfunction "6_6") (pintype "passive"))
    )
    (net (code "6") (name "CHARGE") (class "Default")
      (node (ref "S1") (pin "P$3") (pinfunction "N/O_P$3") (pintype "bidirectional"))
      (node (ref "S2") (pin "P$3") (pinfunction "N/O_P$3") (pintype "bidirectional"))
      (node (ref "S3") (pin "P$3") (pinfunction "N/O_P$3") (pintype "bidirectional"))
      (node (ref "S4") (pin "P$3") (pinfunction "N/O_P$3") (pintype "bidirectional"))
      (node (ref "U$2") (pin "1") (pinfunction "1_1") (pintype "passive"))
      (node (ref "U$4") (pin "1") (pinfunction "1_1") (pintype "passive"))
      (node (ref "U$6") (pin "1") (pinfunction "1_1") (pintype "passive"))
      (node (ref "U$8") (pin "1") (pinfunction "1_1") (pintype "passive"))
    )
    (net (code "7") (name "DIO0") (class "Default")
      (node (ref "IC10") (pin "11") (pinfunction "IO26_11") (pintype "bidirectional"))
      (node (ref "IC15") (pin "11") (pinfunction "IO26_11") (pintype "bidirectional"))
      (node (ref "IC3") (pin "11") (pinfunction "IO26_11") (pintype "bidirectional"))
      (node (ref "IC5") (pin "11") (pinfunction "IO26_11") (pintype "bidirectional"))
      (node (ref "U1") (pin "14") (pinfunction "DIO0_14") (pintype "bidirectional"))
      (node (ref "U2") (pin "14") (pinfunction "DIO0_14") (pintype "bidirectional"))
      (node (ref "U3") (pin "14") (pinfunction "DIO0_14") (pintype "bidirectional"))
      (node (ref "U4") (pin "14") (pinfunction "DIO0_14") (pintype "bidirectional"))
    )
    (net (code "8") (name "DIO1") (class "Default")
      (node (ref "IC10") (pin "9") (pinfunction "IO33_9") (pintype "bidirectional"))
      (node (ref "IC15") (pin "9") (pinfunction "IO33_9") (pintype "bidirectional"))
      (node (ref "IC3") (pin "9") (pinfunction "IO33_9") (pintype "bidirectional"))
      (node (ref "IC5") (pin "9") (pinfunction "IO33_9") (pintype "bidirectional"))
      (node (ref "U1") (pin "15") (pinfunction "DIO1_15") (pintype "bidirectional"))
      (node (ref "U2") (pin "15") (pinfunction "DIO1_15") (pintype "bidirectional"))
      (node (ref "U3") (pin "15") (pinfunction "DIO1_15") (pintype "bidirectional"))
      (node (ref "U4") (pin "15") (pinfunction "DIO1_15") (pintype "bidirectional"))
    )
    (net (code "9") (name "DIO2") (class "Default")
      (node (ref "IC10") (pin "8") (pinfunction "IO32_8") (pintype "bidirectional"))
      (node (ref "IC15") (pin "8") (pinfunction "IO32_8") (pintype "bidirectional"))
      (node (ref "IC3") (pin "8") (pinfunction "IO32_8") (pintype "bidirectional"))
      (node (ref "IC5") (pin "8") (pinfunction "IO32_8") (pintype "bidirectional"))
      (node (ref "U1") (pin "16") (pinfunction "DIO2_16") (pintype "bidirectional"))
      (node (ref "U2") (pin "16") (pinfunction "DIO2_16") (pintype "bidirectional"))
      (node (ref "U3") (pin "16") (pinfunction "DIO2_16") (pintype "bidirectional"))
      (node (ref "U4") (pin "16") (pinfunction "DIO2_16") (pintype "bidirectional"))
    )
    (net (code "10") (name "DIO5") (class "Default")
      (node (ref "IC10") (pin "10") (pinfunction "IO25_10") (pintype "bidirectional"))
      (node (ref "IC15") (pin "10") (pinfunction "IO25_10") (pintype "bidirectional"))
      (node (ref "IC3") (pin "10") (pinfunction "IO25_10") (pintype "bidirectional"))
      (node (ref "IC5") (pin "10") (pinfunction "IO25_10") (pintype "bidirectional"))
      (node (ref "U1") (pin "7") (pinfunction "DIO5_7") (pintype "bidirectional"))
      (node (ref "U2") (pin "7") (pinfunction "DIO5_7") (pintype "bidirectional"))
      (node (ref "U3") (pin "7") (pinfunction "DIO5_7") (pintype "bidirectional"))
      (node (ref "U4") (pin "7") (pinfunction "DIO5_7") (pintype "bidirectional"))
    )
    (net (code "11") (name "FIX") (class "Default")
      (node (ref "IC10") (pin "6") (pinfunction "IO34_6") (pintype "bidirectional"))
      (node (ref "IC15") (pin "6") (pinfunction "IO34_6") (pintype "bidirectional"))
      (node (ref "IC3") (pin "6") (pinfunction "IO34_6") (pintype "bidirectional"))
      (node (ref "IC5") (pin "6") (pinfunction "IO34_6") (pintype "bidirectional"))
      (node (ref "R22") (pin "1") (pinfunction "1_1") (pintype "passive"))
      (node (ref "R33") (pin "1") (pinfunction "1_1") (pintype "passive"))
      (node (ref "R44") (pin "1") (pinfunction "1_1") (pintype "passive"))
      (node (ref "R7") (pin "1") (pinfunction "1_1") (pintype "passive"))
    )
    (net (code "12") (name "GND") (class "Default")
      (node (ref "C1") (pin "1") (pinfunction "1_1") (pintype "passive"))
      (node (ref "C10") (pin "1") (pinfunction "1_1") (pintype "passive"))
      (node (ref "C12") (pin "1") (pinfunction "1_1") (pintype "passive"))
      (node (ref "C13") (pin "1") (pinfunction "1_1") (pintype "passive"))
      (node (ref "C15") (pin "2") (pinfunction "2_2") (pintype "passive"))
      (node (ref "C16") (pin "2") (pinfunction "2_2") (pintype "passive"))
      (node (ref "C17") (pin "1") (pinfunction "1_1") (pintype "passive"))
      (node (ref "C19") (pin "1") (pinfunction "1_1") (pintype "passive"))
      (node (ref "C20") (pin "1") (pinfunction "1_1") (pintype "passive"))
      (node (ref "C22") (pin "2") (pinfunction "2_2") (pintype "passive"))
      (node (ref "C23") (pin "2") (pinfunction "2_2") (pintype "passive"))
      (node (ref "C24") (pin "1") (pinfunction "1_1") (pintype "passive"))
      (node (ref "C26") (pin "1") (pinfunction "1_1") (pintype "passive"))
      (node (ref "C27") (pin "1") (pinfunction "1_1") (pintype "passive"))
      (node (ref "C3") (pin "1") (pinfunction "1_1") (pintype "passive"))
      (node (ref "C4") (pin "1") (pinfunction "1_1") (pintype "passive"))
      (node (ref "C5") (pin "2") (pinfunction "2_2") (pintype "passive"))
      (node (ref "C6") (pin "2") (pinfunction "2_2") (pintype "passive"))
      (node (ref "C7") (pin "2") (pinfunction "2_2") (pintype "passive"))
      (node (ref "C8") (pin "2") (pinfunction "2_2") (pintype "passive"))
      (node (ref "CN1") (pin "2") (pinfunction "1_2") (pintype "passive"))
      (node (ref "CN2") (pin "2") (pinfunction "1_2") (pintype "passive"))
      (node (ref "CN3") (pin "2") (pinfunction "1_2") (pintype "passive"))
      (node (ref "CN4") (pin "2") (pinfunction "1_2") (pintype "passive"))
      (node (ref "IC1") (pin "1") (pinfunction "GND_1") (pintype "bidirectional"))
      (node (ref "IC10") (pin "1") (pinfunction "GND_1") (pintype "bidirectional"))
      (node (ref "IC10") (pin "15") (pinfunction "GND_15") (pintype "bidirectional"))
      (node (ref "IC10") (pin "38") (pinfunction "GND_38") (pintype "bidirectional"))
      (node (ref "IC10") (pin "GND") (pinfunction "GND_GND") (pintype "bidirectional"))
      (node (ref "IC11") (pin "1") (pinfunction "GND_1") (pintype "bidirectional"))
      (node (ref "IC12") (pin "2") (pinfunction "GND_2") (pintype "power_in"))
      (node (ref "IC13") (pin "P$1") (pinfunction "GND_P$1") (pintype "bidirectional"))
      (node (ref "IC13") (pin "P$10") (pinfunction "GND_P$10") (pintype "bidirectional"))
      (node (ref "IC13") (pin "P$12") (pinfunction "GND_P$12") (pintype "bidirectional"))
      (node (ref "IC14") (pin "1") (pinfunction "GND_1") (pintype "power_in"))
      (node (ref "IC14") (pin "2") (pinfunction "GND_2") (pintype "power_in"))
      (node (ref "IC15") (pin "1") (pinfunction "GND_1") (pintype "bidirectional"))
      (node (ref "IC15") (pin "15") (pinfunction "GND_15") (pintype "bidirectional"))
      (node (ref "IC15") (pin "38") (pinfunction "GND_38") (pintype "bidirectional"))
      (node (ref "IC15") (pin "GND") (pinfunction "GND_GND") (pintype "bidirectional"))
      (node (ref "IC16") (pin "1") (pinfunction "GND_1") (pintype "bidirectional"))
      (node (ref "IC17") (pin "2") (pinfunction "GND_2") (pintype "power_in"))
      (node (ref "IC18") (pin "P$1") (pinfunction "GND_P$1") (pintype "bidirectional"))
      (node (ref "IC18") (pin "P$10") (pinfunction "GND_P$10") (pintype "bidirectional"))
      (node (ref "IC18") (pin "P$12") (pinfunction "GND_P$12") (pintype "bidirectional"))
      (node (ref "IC19") (pin "1") (pinfunction "GND_1") (pintype "power_in"))
      (node (ref "IC19") (pin "2") (pinfunction "GND_2") (pintype "power_in"))
      (node (ref "IC2") (pin "2") (pinfunction "GND_2") (pintype "power_in"))
      (node (ref "IC3") (pin "1") (pinfunction "GND_1") (pintype "bidirectional"))
      (node (ref "IC3") (pin "15") (pinfunction "GND_15") (pintype "bidirectional"))
      (node (ref "IC3") (pin "38") (pinfunction "GND_38") (pintype "bidirectional"))
      (node (ref "IC3") (pin "GND") (pinfunction "GND_GND") (pintype "bidirectional"))
      (node (ref "IC4") (pin "1") (pinfunction "GND_1") (pintype "power_in"))
      (node (ref "IC4") (pin "2") (pinfunction "GND_2") (pintype "power_in"))
      (node (ref "IC5") (pin "1") (pinfunction "GND_1") (pintype "bidirectional"))
      (node (ref "IC5") (pin "15") (pinfunction "GND_15") (pintype "bidirectional"))
      (node (ref "IC5") (pin "38") (pinfunction "GND_38") (pintype "bidirectional"))
      (node (ref "IC5") (pin "GND") (pinfunction "GND_GND") (pintype "bidirectional"))
      (node (ref "IC54") (pin "P$1") (pinfunction "GND_P$1") (pintype "bidirectional"))
      (node (ref "IC54") (pin "P$10") (pinfunction "GND_P$10") (pintype "bidirectional"))
      (node (ref "IC54") (pin "P$12") (pinfunction "GND_P$12") (pintype "bidirectional"))
      (node (ref "IC6") (pin "1") (pinfunction "GND_1") (pintype "bidirectional"))
      (node (ref "IC7") (pin "2") (pinfunction "GND_2") (pintype "power_in"))
      (node (ref "IC8") (pin "P$1") (pinfunction "GND_P$1") (pintype "bidirectional"))
      (node (ref "IC8") (pin "P$10") (pinfunction "GND_P$10") (pintype "bidirectional"))
      (node (ref "IC8") (pin "P$12") (pinfunction "GND_P$12") (pintype "bidirectional"))
      (node (ref "IC9") (pin "1") (pinfunction "GND_1") (pintype "power_in"))
      (node (ref "IC9") (pin "2") (pinfunction "GND_2") (pintype "power_in"))
      (node (ref "J1") (pin "1") (pinfunction "GND_1") (pintype "bidirectional"))
      (node (ref "J1") (pin "2") (pinfunction "GND_2") (pintype "bidirectional"))
      (node (ref "J2") (pin "1") (pinfunction "GND_1") (pintype "bidirectional"))
      (node (ref "J2") (pin "2") (pinfunction "GND_2") (pintype "bidirectional"))
      (node (ref "J3") (pin "1") (pinfunction "GND_1") (pintype "bidirectional"))
      (node (ref "J3") (pin "2") (pinfunction "GND_2") (pintype "bidirectional"))
      (node (ref "J4") (pin "1") (pinfunction "GND_1") (pintype "bidirectional"))
      (node (ref "J4") (pin "2") (pinfunction "GND_2") (pintype "bidirectional"))
      (node (ref "J5") (pin "1") (pinfunction "GND_1") (pintype "bidirectional"))
      (node (ref "J5") (pin "2") (pinfunction "GND_2") (pintype "bidirectional"))
      (node (ref "J6") (pin "1") (pinfunction "GND_1") (pintype "bidirectional"))
      (node (ref "J6") (pin "2") (pinfunction "GND_2") (pintype "bidirectional"))
      (node (ref "J7") (pin "1") (pinfunction "GND_1") (pintype "bidirectional"))
      (node (ref "J7") (pin "2") (pinfunction "GND_2") (pintype "bidirectional"))
      (node (ref "J8") (pin "1") (pinfunction "GND_1") (pintype "bidirectional"))
      (node (ref "J8") (pin "2") (pinfunction "GND_2") (pintype "bidirectional"))
      (node (ref "JP1") (pin "2") (pinfunction "2_2") (pintype "passive"))
      (node (ref "JP2") (pin "2") (pinfunction "2_2") (pintype "passive"))
      (node (ref "JP3") (pin "2") (pinfunction "2_2") (pintype "passive"))
      (node (ref "JP4") (pin "2") (pinfunction "2_2") (pintype "passive"))
      (node (ref "LED1") (pin "C") (pinfunction "C_C") (pintype "passive"))
      (node (ref "LED10") (pin "C") (pinfunction "C_C") (pintype "passive"))
      (node (ref "LED12") (pin "C") (pinfunction "C_C") (pintype "passive"))
      (node (ref "LED13") (pin "C") (pinfunction "C_C") (pintype "passive"))
      (node (ref "LED14") (pin "C") (pinfunction "C_C") (pintype "passive"))
      (node (ref "LED16") (pin "C") (pinfunction "C_C") (pintype "passive"))
      (node (ref "LED2") (pin "C") (pinfunction "C_C") (pintype "passive"))
      (node (ref "LED4") (pin "C") (pinfunction "C_C") (pintype "passive"))
      (node (ref "LED5") (pin "C") (pinfunction "C_C") (pintype "passive"))
      (node (ref "LED6") (pin "C") (pinfunction "C_C") (pintype "passive"))
      (node (ref "LED8") (pin "C") (pinfunction "C_C") (pintype "passive"))
      (node (ref "LED9") (pin "C") (pinfunction "C_C") (pintype "passive"))
      (node (ref "R11") (pin "2") (pinfunction "2_2") (pintype "passive"))
      (node (ref "R13") (pin "2") (pinfunction "2_2") (pintype "passive"))
      (node (ref "R2") (pin "2") (pinfunction "2_2") (pintype "passive"))
      (node (ref "R20") (pin "2") (pinfunction "2_2") (pintype "passive"))
      (node (ref "R24") (pin "2") (pinfunction "2_2") (pintype "passive"))
      (node (ref "R31") (pin "2") (pinfunction "2_2") (pintype "passive"))
      (node (ref "R35") (pin "2") (pinfunction "2_2") (pintype "passive"))
      (node (ref "R42") (pin "2") (pinfunction "2_2") (pintype "passive"))
      (node (ref "U$1") (pin "1") (pinfunction "GND_1") (pintype "power_in"))
      (node (ref "U$2") (pin "7") (pinfunction "7_7") (pintype "passive"))
      (node (ref "U$3") (pin "1") (pinfunction "GND_1") (pintype "power_in"))
      (node (ref "U$4") (pin "7") (pinfunction "7_7") (pintype "passive"))
      (node (ref "U$5") (pin "1") (pinfunction "GND_1") (pintype "power_in"))
      (node (ref "U$6") (pin "7") (pinfunction "7_7") (pintype "passive"))
      (node (ref "U$7") (pin "1") (pinfunction "GND_1") (pintype "power_in"))
      (node (ref "U$8") (pin "7") (pinfunction "7_7") (pintype "passive"))
      (node (ref "U1") (pin "1") (pinfunction "GND_1") (pintype "power_in"))
      (node (ref "U1") (pin "10") (pinfunction "GND_10") (pintype "power_in"))
      (node (ref "U1") (pin "8") (pinfunction "GND_8") (pintype "power_in"))
      (node (ref "U2") (pin "1") (pinfunction "GND_1") (pintype "power_in"))
      (node (ref "U2") (pin "10") (pinfunction "GND_10") (pintype "power_in"))
      (node (ref "U2") (pin "8") (pinfunction "GND_8") (pintype "power_in"))
      (node (ref "U3") (pin "1") (pinfunction "GND_1") (pintype "power_in"))
      (node (ref "U3") (pin "10") (pinfunction "GND_10") (pintype "power_in"))
      (node (ref "U3") (pin "8") (pinfunction "GND_8") (pintype "power_in"))
      (node (ref "U4") (pin "1") (pinfunction "GND_1") (pintype "power_in"))
      (node (ref "U4") (pin "10") (pinfunction "GND_10") (pintype "power_in"))
      (node (ref "U4") (pin "8") (pinfunction "GND_8") (pintype "power_in"))
    )
    (net (code "13") (name "GPS_PWR") (class "Default")
      (node (ref "IC10") (pin "16") (pinfunction "IO13_16") (pintype "bidirectional"))
      (node (ref "IC15") (pin "16") (pinfunction "IO13_16") (pintype "bidirectional"))
      (node (ref "IC3") (pin "16") (pinfunction "IO13_16") (pintype "bidirectional"))
      (node (ref "IC5") (pin "16") (pinfunction "IO13_16") (pintype "bidirectional"))
    )
    (net (code "14") (name "GPS_RX") (class "Default")
      (node (ref "IC10") (pin "23") (pinfunction "IO15_23") (pintype "bidirectional"))
      (node (ref "IC13") (pin "P$2") (pinfunction "TXD_P$2") (pintype "bidirectional"))
      (node (ref "IC15") (pin "23") (pinfunction "IO15_23") (pintype "bidirectional"))
      (node (ref "IC18") (pin "P$2") (pinfunction "TXD_P$2") (pintype "bidirectional"))
      (node (ref "IC3") (pin "23") (pinfunction "IO15_23") (pintype "bidirectional"))
      (node (ref "IC5") (pin "23") (pinfunction "IO15_23") (pintype "bidirectional"))
      (node (ref "IC54") (pin "P$2") (pinfunction "TXD_P$2") (pintype "bidirectional"))
      (node (ref "IC8") (pin "P$2") (pinfunction "TXD_P$2") (pintype "bidirectional"))
    )
    (net (code "15") (name "GPS_TX") (class "Default")
      (node (ref "IC10") (pin "14") (pinfunction "IO12_14") (pintype "bidirectional"))
      (node (ref "IC13") (pin "P$3") (pinfunction "RXD_P$3") (pintype "bidirectional"))
      (node (ref "IC15") (pin "14") (pinfunction "IO12_14") (pintype "bidirectional"))
      (node (ref "IC18") (pin "P$3") (pinfunction "RXD_P$3") (pintype "bidirectional"))
      (node (ref "IC3") (pin "14") (pinfunction "IO12_14") (pintype "bidirectional"))
      (node (ref "IC5") (pin "14") (pinfunction "IO12_14") (pintype "bidirectional"))
      (node (ref "IC54") (pin "P$3") (pinfunction "RXD_P$3") (pintype "bidirectional"))
      (node (ref "IC8") (pin "P$3") (pinfunction "RXD_P$3") (pintype "bidirectional"))
    )
    (net (code "16") (name "LED") (class "Default")
      (node (ref "IC10") (pin "13") (pinfunction "IO14_13") (pintype "bidirectional"))
      (node (ref "IC15") (pin "13") (pinfunction "IO14_13") (pintype "bidirectional"))
      (node (ref "IC3") (pin "13") (pinfunction "IO14_13") (pintype "bidirectional"))
      (node (ref "IC5") (pin "13") (pinfunction "IO14_13") (pintype "bidirectional"))
      (node (ref "R14") (pin "1") (pinfunction "1_1") (pintype "passive"))
      (node (ref "R25") (pin "1") (pinfunction "1_1") (pintype "passive"))
      (node (ref "R3") (pin "1") (pinfunction "1_1") (pintype "passive"))
      (node (ref "R36") (pin "1") (pinfunction "1_1") (pintype "passive"))
    )
    (net (code "17") (name "MISO") (class "Default")
      (node (ref "IC10") (pin "31") (pinfunction "IO19_31") (pintype "bidirectional"))
      (node (ref "IC15") (pin "31") (pinfunction "IO19_31") (pintype "bidirectional"))
      (node (ref "IC3") (pin "31") (pinfunction "IO19_31") (pintype "bidirectional"))
      (node (ref "IC5") (pin "31") (pinfunction "IO19_31") (pintype "bidirectional"))
      (node (ref "U1") (pin "2") (pinfunction "MISO_2") (pintype "input"))
      (node (ref "U2") (pin "2") (pinfunction "MISO_2") (pintype "input"))
      (node (ref "U3") (pin "2") (pinfunction "MISO_2") (pintype "input"))
      (node (ref "U4") (pin "2") (pinfunction "MISO_2") (pintype "input"))
    )
    (net (code "18") (name "MOSI") (class "Default")
      (node (ref "IC10") (pin "12") (pinfunction "IO27_12") (pintype "bidirectional"))
      (node (ref "IC15") (pin "12") (pinfunction "IO27_12") (pintype "bidirectional"))
      (node (ref "IC3") (pin "12") (pinfunction "IO27_12") (pintype "bidirectional"))
      (node (ref "IC5") (pin "12") (pinfunction "IO27_12") (pintype "bidirectional"))
      (node (ref "U1") (pin "3") (pinfunction "MOSI_3") (pintype "output"))
      (node (ref "U2") (pin "3") (pinfunction "MOSI_3") (pintype "output"))
      (node (ref "U3") (pin "3") (pinfunction "MOSI_3") (pintype "output"))
      (node (ref "U4") (pin "3") (pinfunction "MOSI_3") (pintype "output"))
    )
    (net (code "19") (name "N$8") (class "Default")
      (node (ref "IC13") (pin "P$9") (pinfunction "NRESET_P$9") (pintype "bidirectional"))
      (node (ref "IC18") (pin "P$9") (pinfunction "NRESET_P$9") (pintype "bidirectional"))
      (node (ref "IC54") (pin "P$9") (pinfunction "NRESET_P$9") (pintype "bidirectional"))
      (node (ref "IC8") (pin "P$9") (pinfunction "NRESET_P$9") (pintype "bidirectional"))
    )
    (net (code "20") (name "NSS") (class "Default")
      (node (ref "IC10") (pin "30") (pinfunction "IO18_30") (pintype "bidirectional"))
      (node (ref "IC15") (pin "30") (pinfunction "IO18_30") (pintype "bidirectional"))
      (node (ref "IC3") (pin "30") (pinfunction "IO18_30") (pintype "bidirectional"))
      (node (ref "IC5") (pin "30") (pinfunction "IO18_30") (pintype "bidirectional"))
      (node (ref "U1") (pin "5") (pinfunction "NSS_5") (pintype "input"))
      (node (ref "U2") (pin "5") (pinfunction "NSS_5") (pintype "input"))
      (node (ref "U3") (pin "5") (pinfunction "NSS_5") (pintype "input"))
      (node (ref "U4") (pin "5") (pinfunction "NSS_5") (pintype "input"))
    )
    (net (code "21") (name "Net-(C9-Pad1)") (class "Default")
      (node (ref "C9") (pin "1") (pinfunction "1_1") (pintype "passive"))
      (node (ref "L2") (pin "1") (pinfunction "1_1") (pintype "passive"))
    )
    (net (code "22") (name "Net-(C14-Pad1)") (class "Default")
      (node (ref "C14") (pin "1") (pinfunction "1_1") (pintype "passive"))
      (node (ref "L4") (pin "1") (pinfunction "1_1") (pintype "passive"))
    )
    (net (code "23") (name "Net-(C21-Pad1)") (class "Default")
      (node (ref "C21") (pin "1") (pinfunction "1_1") (pintype "passive"))
      (node (ref "L6") (pin "1") (pinfunction "1_1") (pintype "passive"))
    )
    (net (code "24") (name "Net-(C28-Pad1)") (class "Default")
      (node (ref "C28") (pin "1") (pinfunction "1_1") (pintype "passive"))
      (node (ref "L8") (pin "1") (pinfunction "1_1") (pintype "passive"))
    )
    (net (code "25") (name "Net-(IC2-FB)") (class "Default")
      (node (ref "C2") (pin "1") (pinfunction "1_1") (pintype "passive"))
      (node (ref "IC2") (pin "3") (pinfunction "FB_3") (pintype "input"))
      (node (ref "R1") (pin "2") (pinfunction "2_2") (pintype "passive"))
      (node (ref "R2") (pin "1") (pinfunction "1_1") (pintype "passive"))
    )
    (net (code "26") (name "Net-(IC2-SW)") (class "Default")
      (node (ref "D1") (pin "A") (pinfunction "A_A") (pintype "passive"))
      (node (ref "IC2") (pin "1") (pinfunction "SW_1") (pintype "bidirectional"))
      (node (ref "L1") (pin "P$2") (pinfunction "2_P$2") (pintype "passive"))
    )
    (net (code "27") (name "Net-(IC4-RFIN)") (class "Default")
      (node (ref "IC4") (pin "3") (pinfunction "RFIN_3") (pintype "input"))
      (node (ref "L2") (pin "2") (pinfunction "2_2") (pintype "passive"))
    )
    (net (code "28") (name "Net-(IC4-RFOUT)") (class "Default")
      (node (ref "IC4") (pin "6") (pinfunction "RFOUT_6") (pintype "output"))
      (node (ref "IC54") (pin "P$11") (pinfunction "RF_IN_P$11") (pintype "bidirectional"))
    )
    (net (code "29") (name "Net-(IC7-FB)") (class "Default")
      (node (ref "C11") (pin "1") (pinfunction "1_1") (pintype "passive"))
      (node (ref "IC7") (pin "3") (pinfunction "FB_3") (pintype "input"))
      (node (ref "R13") (pin "1") (pinfunction "1_1") (pintype "passive"))
      (node (ref "R8") (pin "2") (pinfunction "2_2") (pintype "passive"))
    )
    (net (code "30") (name "Net-(IC7-SW)") (class "Default")
      (node (ref "D2") (pin "A") (pinfunction "A_A") (pintype "passive"))
      (node (ref "IC7") (pin "1") (pinfunction "SW_1") (pintype "bidirectional"))
      (node (ref "L3") (pin "P$2") (pinfunction "2_P$2") (pintype "passive"))
    )
    (net (code "31") (name "Net-(IC8-RF_IN)") (class "Default")
      (node (ref "IC8") (pin "P$11") (pinfunction "RF_IN_P$11") (pintype "bidirectional"))
      (node (ref "IC9") (pin "6") (pinfunction "RFOUT_6") (pintype "output"))
    )
    (net (code "32") (name "Net-(IC9-RFIN)") (class "Default")
      (node (ref "IC9") (pin "3") (pinfunction "RFIN_3") (pintype "input"))
      (node (ref "L4") (pin "2") (pinfunction "2_2") (pintype "passive"))
    )
    (net (code "33") (name "Net-(IC12-FB)") (class "Default")
      (node (ref "C18") (pin "1") (pinfunction "1_1") (pintype "passive"))
      (node (ref "IC12") (pin "3") (pinfunction "FB_3") (pintype "input"))
      (node (ref "R23") (pin "2") (pinfunction "2_2") (pintype "passive"))
      (node (ref "R24") (pin "1") (pinfunction "1_1") (pintype "passive"))
    )
    (net (code "34") (name "Net-(IC12-SW)") (class "Default")
      (node (ref "D3") (pin "A") (pinfunction "A_A") (pintype "passive"))
      (node (ref "IC12") (pin "1") (pinfunction "SW_1") (pintype "bidirectional"))
      (node (ref "L5") (pin "P$2") (pinfunction "2_P$2") (pintype "passive"))
    )
    (net (code "35") (name "Net-(IC13-RF_IN)") (class "Default")
      (node (ref "IC13") (pin "P$11") (pinfunction "RF_IN_P$11") (pintype "bidirectional"))
      (node (ref "IC14") (pin "6") (pinfunction "RFOUT_6") (pintype "output"))
    )
    (net (code "36") (name "Net-(IC14-RFIN)") (class "Default")
      (node (ref "IC14") (pin "3") (pinfunction "RFIN_3") (pintype "input"))
      (node (ref "L6") (pin "2") (pinfunction "2_2") (pintype "passive"))
    )
    (net (code "37") (name "Net-(IC17-FB)") (class "Default")
      (node (ref "C25") (pin "1") (pinfunction "1_1") (pintype "passive"))
      (node (ref "IC17") (pin "3") (pinfunction "FB_3") (pintype "input"))
      (node (ref "R34") (pin "2") (pinfunction "2_2") (pintype "passive"))
      (node (ref "R35") (pin "1") (pinfunction "1_1") (pintype "passive"))
    )
    (net (code "38") (name "Net-(IC17-SW)") (class "Default")
      (node (ref "D4") (pin "A") (pinfunction "A_A") (pintype "passive"))
      (node (ref "IC17") (pin "1") (pinfunction "SW_1") (pintype "bidirectional"))
      (node (ref "L7") (pin "P$2") (pinfunction "2_P$2") (pintype "passive"))
    )
    (net (code "39") (name "Net-(IC18-RF_IN)") (class "Default")
      (node (ref "IC18") (pin "P$11") (pinfunction "RF_IN_P$11") (pintype "bidirectional"))
      (node (ref "IC19") (pin "6") (pinfunction "RFOUT_6") (pintype "output"))
    )
    (net (code "40") (name "Net-(IC19-RFIN)") (class "Default")
      (node (ref "IC19") (pin "3") (pinfunction "RFIN_3") (pintype "input"))
      (node (ref "L8") (pin "2") (pinfunction "2_2") (pintype "passive"))
    )
    (net (code "41") (name "Net-(J1-SIGNAL)") (class "Default")
      (node (ref "C9") (pin "2") (pinfunction "2_2") (pintype "passive"))
      (node (ref "J1") (pin "FEED") (pinfunction "SIGNAL_FEED") (pintype "bidirectional"))
    )
    (net (code "42") (name "Net-(J2-SIGNAL)") (class "Default")
      (node (ref "J2") (pin "FEED") (pinfunction "SIGNAL_FEED") (pintype "bidirectional"))
      (node (ref "U2") (pin "9") (pinfunction "ANT_9") (pintype "bidirectional"))
    )
    (net (code "43") (name "Net-(J3-SIGNAL)") (class "Default")
      (node (ref "J3") (pin "FEED") (pinfunction "SIGNAL_FEED") (pintype "bidirectional"))
      (node (ref "U1") (pin "9") (pinfunction "ANT_9") (pintype "bidirectional"))
    )
    (net (code "44") (name "Net-(J4-SIGNAL)") (class "Default")
      (node (ref "C14") (pin "2") (pinfunction "2_2") (pintype "passive"))
      (node (ref "J4") (pin "FEED") (pinfunction "SIGNAL_FEED") (pintype "bidirectional"))
    )
    (net (code "45") (name "Net-(J5-SIGNAL)") (class "Default")
      (node (ref "J5") (pin "FEED") (pinfunction "SIGNAL_FEED") (pintype "bidirectional"))
      (node (ref "U3") (pin "9") (pinfunction "ANT_9") (pintype "bidirectional"))
    )
    (net (code "46") (name "Net-(J6-SIGNAL)") (class "Default")
      (node (ref "C21") (pin "2") (pinfunction "2_2") (pintype "passive"))
      (node (ref "J6") (pin "FEED") (pinfunction "SIGNAL_FEED") (pintype "bidirectional"))
    )
    (net (code "47") (name "Net-(J7-SIGNAL)") (class "Default")
      (node (ref "J7") (pin "FEED") (pinfunction "SIGNAL_FEED") (pintype "bidirectional"))
      (node (ref "U4") (pin "9") (pinfunction "ANT_9") (pintype "bidirectional"))
    )
    (net (code "48") (name "Net-(J8-SIGNAL)") (class "Default")
      (node (ref "C28") (pin "2") (pinfunction "2_2") (pintype "passive"))
      (node (ref "J8") (pin "FEED") (pinfunction "SIGNAL_FEED") (pintype "bidirectional"))
    )
    (net (code "49") (name "Net-(LED1-PadA)") (class "Default")
      (node (ref "LED1") (pin "A") (pinfunction "A_A") (pintype "passive"))
      (node (ref "R3") (pin "2") (pinfunction "2_2") (pintype "passive"))
    )
    (net (code "50") (name "Net-(LED2-PadA)") (class "Default")
      (node (ref "LED2") (pin "A") (pinfunction "A_A") (pintype "passive"))
      (node (ref "R6") (pin "2") (pinfunction "2_2") (pintype "passive"))
    )
    (net (code "51") (name "Net-(LED3-PadC)") (class "Default")
      (node (ref "LED3") (pin "C") (pinfunction "C_C") (pintype "passive"))
      (node (ref "R10") (pin "2") (pinfunction "2_2") (pintype "passive"))
    )
    (net (code "52") (name "Net-(LED4-PadA)") (class "Default")
      (node (ref "LED4") (pin "A") (pinfunction "A_A") (pintype "passive"))
      (node (ref "R7") (pin "2") (pinfunction "2_2") (pintype "passive"))
    )
    (net (code "53") (name "Net-(LED5-PadA)") (class "Default")
      (node (ref "LED5") (pin "A") (pinfunction "A_A") (pintype "passive"))
      (node (ref "R14") (pin "2") (pinfunction "2_2") (pintype "passive"))
    )
    (net (code "54") (name "Net-(LED6-PadA)") (class "Default")
      (node (ref "LED6") (pin "A") (pinfunction "A_A") (pintype "passive"))
      (node (ref "R17") (pin "2") (pinfunction "2_2") (pintype "passive"))
    )
    (net (code "55") (name "Net-(LED7-PadC)") (class "Default")
      (node (ref "LED7") (pin "C") (pinfunction "C_C") (pintype "passive"))
      (node (ref "R18") (pin "2") (pinfunction "2_2") (pintype "passive"))
    )
    (net (code "56") (name "Net-(LED8-PadA)") (class "Default")
      (node (ref "LED8") (pin "A") (pinfunction "A_A") (pintype "passive"))
      (node (ref "R22") (pin "2") (pinfunction "2_2") (pintype "passive"))
    )
    (net (code "57") (name "Net-(LED9-PadA)") (class "Default")
      (node (ref "LED9") (pin "A") (pinfunction "A_A") (pintype "passive"))
      (node (ref "R25") (pin "2") (pinfunction "2_2") (pintype "passive"))
    )
    (net (code "58") (name "Net-(LED10-PadA)") (class "Default")
      (node (ref "LED10") (pin "A") (pinfunction "A_A") (pintype "passive"))
      (node (ref "R28") (pin "2") (pinfunction "2_2") (pintype "passive"))
    )
    (net (code "59") (name "Net-(LED11-PadC)") (class "Default")
      (node (ref "LED11") (pin "C") (pinfunction "C_C") (pintype "passive"))
      (node (ref "R29") (pin "2") (pinfunction "2_2") (pintype "passive"))
    )
    (net (code "60") (name "Net-(LED12-PadA)") (class "Default")
      (node (ref "LED12") (pin "A") (pinfunction "A_A") (pintype "passive"))
      (node (ref "R33") (pin "2") (pinfunction "2_2") (pintype "passive"))
    )
    (net (code "61") (name "Net-(LED13-PadA)") (class "Default")
      (node (ref "LED13") (pin "A") (pinfunction "A_A") (pintype "passive"))
      (node (ref "R36") (pin "2") (pinfunction "2_2") (pintype "passive"))
    )
    (net (code "62") (name "Net-(LED14-PadA)") (class "Default")
      (node (ref "LED14") (pin "A") (pinfunction "A_A") (pintype "passive"))
      (node (ref "R39") (pin "2") (pinfunction "2_2") (pintype "passive"))
    )
    (net (code "63") (name "Net-(LED15-PadC)") (class "Default")
      (node (ref "LED15") (pin "C") (pinfunction "C_C") (pintype "passive"))
      (node (ref "R40") (pin "2") (pinfunction "2_2") (pintype "passive"))
    )
    (net (code "64") (name "Net-(LED16-PadA)") (class "Default")
      (node (ref "LED16") (pin "A") (pinfunction "A_A") (pintype "passive"))
      (node (ref "R44") (pin "2") (pinfunction "2_2") (pintype "passive"))
    )
    (net (code "65") (name "Net-(R12-Pad1)") (class "Default")
      (node (ref "R12") (pin "1") (pinfunction "1_1") (pintype "passive"))
      (node (ref "U$2") (pin "10") (pinfunction "10_10") (pintype "passive"))
    )
    (net (code "66") (name "Net-(R21-Pad1)") (class "Default")
      (node (ref "R21") (pin "1") (pinfunction "1_1") (pintype "passive"))
      (node (ref "U$4") (pin "10") (pinfunction "10_10") (pintype "passive"))
    )
    (net (code "67") (name "Net-(R32-Pad1)") (class "Default")
      (node (ref "R32") (pin "1") (pinfunction "1_1") (pintype "passive"))
      (node (ref "U$6") (pin "10") (pinfunction "10_10") (pintype "passive"))
    )
    (net (code "68") (name "Net-(R43-Pad1)") (class "Default")
      (node (ref "R43") (pin "1") (pinfunction "1_1") (pintype "passive"))
      (node (ref "U$8") (pin "10") (pinfunction "10_10") (pintype "passive"))
    )
    (net (code "69") (name "PPS") (class "Default")
      (node (ref "IC13") (pin "P$4") (pinfunction "1PPS_P$4") (pintype "bidirectional"))
      (node (ref "IC18") (pin "P$4") (pinfunction "1PPS_P$4") (pintype "bidirectional"))
      (node (ref "IC54") (pin "P$4") (pinfunction "1PPS_P$4") (pintype "bidirectional"))
      (node (ref "IC8") (pin "P$4") (pinfunction "1PPS_P$4") (pintype "bidirectional"))
      (node (ref "R10") (pin "1") (pinfunction "1_1") (pintype "passive"))
      (node (ref "R18") (pin "1") (pinfunction "1_1") (pintype "passive"))
      (node (ref "R29") (pin "1") (pinfunction "1_1") (pintype "passive"))
      (node (ref "R40") (pin "1") (pinfunction "1_1") (pintype "passive"))
    )
    (net (code "70") (name "PWR") (class "Default")
      (node (ref "C1") (pin "2") (pinfunction "2_2") (pintype "passive"))
      (node (ref "C10") (pin "2") (pinfunction "2_2") (pintype "passive"))
      (node (ref "C17") (pin "2") (pinfunction "2_2") (pintype "passive"))
      (node (ref "C24") (pin "2") (pinfunction "2_2") (pintype "passive"))
      (node (ref "IC12") (pin "4") (pinfunction "EN_4") (pintype "input"))
      (node (ref "IC12") (pin "5") (pinfunction "VIN_5") (pintype "input"))
      (node (ref "IC17") (pin "4") (pinfunction "EN_4") (pintype "input"))
      (node (ref "IC17") (pin "5") (pinfunction "VIN_5") (pintype "input"))
      (node (ref "IC2") (pin "4") (pinfunction "EN_4") (pintype "input"))
      (node (ref "IC2") (pin "5") (pinfunction "VIN_5") (pintype "input"))
      (node (ref "IC7") (pin "4") (pinfunction "EN_4") (pintype "input"))
      (node (ref "IC7") (pin "5") (pinfunction "VIN_5") (pintype "input"))
      (node (ref "L1") (pin "P$1") (pinfunction "1_P$1") (pintype "passive"))
      (node (ref "L3") (pin "P$1") (pinfunction "1_P$1") (pintype "passive"))
      (node (ref "L5") (pin "P$1") (pinfunction "1_P$1") (pintype "passive"))
      (node (ref "L7") (pin "P$1") (pinfunction "1_P$1") (pintype "passive"))
      (node (ref "S1") (pin "P$1") (pinfunction "N/C_P$1") (pintype "bidirectional"))
      (node (ref "S2") (pin "P$1") (pinfunction "N/C_P$1") (pintype "bidirectional"))
      (node (ref "S3") (pin "P$1") (pinfunction "N/C_P$1") (pintype "bidirectional"))
      (node (ref "S4") (pin "P$1") (pinfunction "N/C_P$1") (pintype "bidirectional"))
    )
    (net (code "71") (name "RESET") (class "Default")
      (node (ref "IC10") (pin "37") (pinfunction "IO23_37") (pintype "bidirectional"))
      (node (ref "IC15") (pin "37") (pinfunction "IO23_37") (pintype "bidirectional"))
      (node (ref "IC3") (pin "37") (pinfunction "IO23_37") (pintype "bidirectional"))
      (node (ref "IC5") (pin "37") (pinfunction "IO23_37") (pintype "bidirectional"))
      (node (ref "U1") (pin "6") (pinfunction "RESET_6") (pintype "bidirectional"))
      (node (ref "U2") (pin "6") (pinfunction "RESET_6") (pintype "bidirectional"))
      (node (ref "U3") (pin "6") (pinfunction "RESET_6") (pintype "bidirectional"))
      (node (ref "U4") (pin "6") (pinfunction "RESET_6") (pintype "bidirectional"))
    )
    (net (code "72") (name "RST") (class "Default")
      (node (ref "IC10") (pin "3") (pinfunction "EN_3") (pintype "bidirectional"))
      (node (ref "IC15") (pin "3") (pinfunction "EN_3") (pintype "bidirectional"))
      (node (ref "IC3") (pin "3") (pinfunction "EN_3") (pintype "bidirectional"))
      (node (ref "IC5") (pin "3") (pinfunction "EN_3") (pintype "bidirectional"))
      (node (ref "R15") (pin "1") (pinfunction "1_1") (pintype "passive"))
      (node (ref "R26") (pin "1") (pinfunction "1_1") (pintype "passive"))
      (node (ref "R37") (pin "1") (pinfunction "1_1") (pintype "passive"))
      (node (ref "R4") (pin "1") (pinfunction "1_1") (pintype "passive"))
      (node (ref "U$2") (pin "5") (pinfunction "5_5") (pintype "passive"))
      (node (ref "U$4") (pin "5") (pinfunction "5_5") (pintype "passive"))
      (node (ref "U$6") (pin "5") (pinfunction "5_5") (pintype "passive"))
      (node (ref "U$8") (pin "5") (pinfunction "5_5") (pintype "passive"))
    )
    (net (code "73") (name "RX") (class "Default")
      (node (ref "IC10") (pin "34") (pinfunction "RXD_34") (pintype "bidirectional"))
      (node (ref "IC15") (pin "34") (pinfunction "RXD_34") (pintype "bidirectional"))
      (node (ref "IC3") (pin "34") (pinfunction "RXD_34") (pintype "bidirectional"))
      (node (ref "IC5") (pin "34") (pinfunction "RXD_34") (pintype "bidirectional"))
      (node (ref "U$2") (pin "4") (pinfunction "4_4") (pintype "passive"))
      (node (ref "U$4") (pin "4") (pinfunction "4_4") (pintype "passive"))
      (node (ref "U$6") (pin "4") (pinfunction "4_4") (pintype "passive"))
      (node (ref "U$8") (pin "4") (pinfunction "4_4") (pintype "passive"))
    )
    (net (code "74") (name "SCK") (class "Default")
      (node (ref "IC10") (pin "20") (pinfunction "SCK_20") (pintype "bidirectional"))
      (node (ref "IC15") (pin "20") (pinfunction "SCK_20") (pintype "bidirectional"))
      (node (ref "IC3") (pin "20") (pinfunction "SCK_20") (pintype "bidirectional"))
      (node (ref "IC5") (pin "20") (pinfunction "SCK_20") (pintype "bidirectional"))
    )
    (net (code "75") (name "SCL") (class "Default")
      (node (ref "IC10") (pin "36") (pinfunction "IO22_36") (pintype "bidirectional"))
      (node (ref "IC15") (pin "36") (pinfunction "IO22_36") (pintype "bidirectional"))
      (node (ref "IC3") (pin "36") (pinfunction "IO22_36") (pintype "bidirectional"))
      (node (ref "IC5") (pin "36") (pinfunction "IO22_36") (pintype "bidirectional"))
      (node (ref "JP1") (pin "3") (pinfunction "3_3") (pintype "passive"))
      (node (ref "JP2") (pin "3") (pinfunction "3_3") (pintype "passive"))
      (node (ref "JP3") (pin "3") (pinfunction "3_3") (pintype "passive"))
      (node (ref "JP4") (pin "3") (pinfunction "3_3") (pintype "passive"))
      (node (ref "U$1") (pin "3") (pinfunction "SCL_3") (pintype "bidirectional"))
      (node (ref "U$2") (pin "8") (pinfunction "8_8") (pintype "passive"))
      (node (ref "U$3") (pin "3") (pinfunction "SCL_3") (pintype "bidirectional"))
      (node (ref "U$4") (pin "8") (pinfunction "8_8") (pintype "passive"))
      (node (ref "U$5") (pin "3") (pinfunction "SCL_3") (pintype "bidirectional"))
      (node (ref "U$6") (pin "8") (pinfunction "8_8") (pintype "passive"))
      (node (ref "U$7") (pin "3") (pinfunction "SCL_3") (pintype "bidirectional"))
      (node (ref "U$8") (pin "8") (pinfunction "8_8") (pintype "passive"))
    )
    (net (code "76") (name "SCLK") (class "Default")
      (node (ref "IC10") (pin "29") (pinfunction "IO5_29") (pintype "bidirectional"))
      (node (ref "IC15") (pin "29") (pinfunction "IO5_29") (pintype "bidirectional"))
      (node (ref "IC3") (pin "29") (pinfunction "IO5_29") (pintype "bidirectional"))
      (node (ref "IC5") (pin "29") (pinfunction "IO5_29") (pintype "bidirectional"))
      (node (ref "U1") (pin "4") (pinfunction "SCK_4") (pintype "input"))
      (node (ref "U2") (pin "4") (pinfunction "SCK_4") (pintype "input"))
      (node (ref "U3") (pin "4") (pinfunction "SCK_4") (pintype "input"))
      (node (ref "U4") (pin "4") (pinfunction "SCK_4") (pintype "input"))
    )
    (net (code "77") (name "SCS") (class "Default")
      (node (ref "IC10") (pin "19") (pinfunction "SCS_19") (pintype "bidirectional"))
      (node (ref "IC15") (pin "19") (pinfunction "SCS_19") (pintype "bidirectional"))
      (node (ref "IC3") (pin "19") (pinfunction "SCS_19") (pintype "bidirectional"))
      (node (ref "IC5") (pin "19") (pinfunction "SCS_19") (pintype "bidirectional"))
    )
    (net (code "78") (name "SDA") (class "Default")
      (node (ref "IC10") (pin "33") (pinfunction "IO21_33") (pintype "bidirectional"))
      (node (ref "IC15") (pin "33") (pinfunction "IO21_33") (pintype "bidirectional"))
      (node (ref "IC3") (pin "33") (pinfunction "IO21_33") (pintype "bidirectional"))
      (node (ref "IC5") (pin "33") (pinfunction "IO21_33") (pintype "bidirectional"))
      (node (ref "JP1") (pin "4") (pinfunction "4_4") (pintype "passive"))
      (node (ref "JP2") (pin "4") (pinfunction "4_4") (pintype "passive"))
      (node (ref "JP3") (pin "4") (pinfunction "4_4") (pintype "passive"))
      (node (ref "JP4") (pin "4") (pinfunction "4_4") (pintype "passive"))
      (node (ref "U$1") (pin "4") (pinfunction "SDA_4") (pintype "bidirectional"))
      (node (ref "U$2") (pin "9") (pinfunction "9_9") (pintype "passive"))
      (node (ref "U$3") (pin "4") (pinfunction "SDA_4") (pintype "bidirectional"))
      (node (ref "U$4") (pin "9") (pinfunction "9_9") (pintype "passive"))
      (node (ref "U$5") (pin "4") (pinfunction "SDA_4") (pintype "bidirectional"))
      (node (ref "U$6") (pin "9") (pinfunction "9_9") (pintype "passive"))
      (node (ref "U$7") (pin "4") (pinfunction "SDA_4") (pintype "bidirectional"))
      (node (ref "U$8") (pin "9") (pinfunction "9_9") (pintype "passive"))
    )
    (net (code "79") (name "SDI") (class "Default")
      (node (ref "IC10") (pin "22") (pinfunction "SDI_22") (pintype "bidirectional"))
      (node (ref "IC15") (pin "22") (pinfunction "SDI_22") (pintype "bidirectional"))
      (node (ref "IC3") (pin "22") (pinfunction "SDI_22") (pintype "bidirectional"))
      (node (ref "IC5") (pin "22") (pinfunction "SDI_22") (pintype "bidirectional"))
    )
    (net (code "80") (name "SDO") (class "Default")
      (node (ref "IC10") (pin "21") (pinfunction "SDO_21") (pintype "bidirectional"))
      (node (ref "IC15") (pin "21") (pinfunction "SDO_21") (pintype "bidirectional"))
      (node (ref "IC3") (pin "21") (pinfunction "SDO_21") (pintype "bidirectional"))
      (node (ref "IC5") (pin "21") (pinfunction "SDO_21") (pintype "bidirectional"))
    )
    (net (code "81") (name "SHD") (class "Default")
      (node (ref "IC10") (pin "17") (pinfunction "SHD_17") (pintype "bidirectional"))
      (node (ref "IC15") (pin "17") (pinfunction "SHD_17") (pintype "bidirectional"))
      (node (ref "IC3") (pin "17") (pinfunction "SHD_17") (pintype "bidirectional"))
      (node (ref "IC5") (pin "17") (pinfunction "SHD_17") (pintype "bidirectional"))
    )
    (net (code "82") (name "SWP") (class "Default")
      (node (ref "IC10") (pin "18") (pinfunction "SWP_18") (pintype "bidirectional"))
      (node (ref "IC15") (pin "18") (pinfunction "SWP_18") (pintype "bidirectional"))
      (node (ref "IC3") (pin "18") (pinfunction "SWP_18") (pintype "bidirectional"))
      (node (ref "IC5") (pin "18") (pinfunction "SWP_18") (pintype "bidirectional"))
    )
    (net (code "83") (name "TX") (class "Default")
      (node (ref "IC10") (pin "35") (pinfunction "TXD_35") (pintype "bidirectional"))
      (node (ref "IC15") (pin "35") (pinfunction "TXD_35") (pintype "bidirectional"))
      (node (ref "IC3") (pin "35") (pinfunction "TXD_35") (pintype "bidirectional"))
      (node (ref "IC5") (pin "35") (pinfunction "TXD_35") (pintype "bidirectional"))
      (node (ref "U$2") (pin "3") (pinfunction "3_3") (pintype "passive"))
      (node (ref "U$4") (pin "3") (pinfunction "3_3") (pintype "passive"))
      (node (ref "U$6") (pin "3") (pinfunction "3_3") (pintype "passive"))
      (node (ref "U$8") (pin "3") (pinfunction "3_3") (pintype "passive"))
    )
    (net (code "84") (name "VIN") (class "Default")
      (node (ref "CN1") (pin "1") (pinfunction "2_1") (pintype "passive"))
      (node (ref "CN2") (pin "1") (pinfunction "2_1") (pintype "passive"))
      (node (ref "CN3") (pin "1") (pinfunction "2_1") (pintype "passive"))
      (node (ref "CN4") (pin "1") (pinfunction "2_1") (pintype "passive"))
      (node (ref "R19") (pin "2") (pinfunction "2_2") (pintype "passive"))
      (node (ref "R30") (pin "2") (pinfunction "2_2") (pintype "passive"))
      (node (ref "R41") (pin "2") (pinfunction "2_2") (pintype "passive"))
      (node (ref "R9") (pin "2") (pinfunction "2_2") (pintype "passive"))
      (node (ref "S1") (pin "P$2") (pinfunction "COM_P$2") (pintype "bidirectional"))
      (node (ref "S2") (pin "P$2") (pinfunction "COM_P$2") (pintype "bidirectional"))
      (node (ref "S3") (pin "P$2") (pinfunction "COM_P$2") (pintype "bidirectional"))
      (node (ref "S4") (pin "P$2") (pinfunction "COM_P$2") (pintype "bidirectional"))
    )
    (net (code "85") (name "unconnected-(IC3-IO2-Pad24)") (class "Default")
      (node (ref "IC3") (pin "24") (pinfunction "IO2_24") (pintype "bidirectional"))
    )
    (net (code "86") (name "unconnected-(IC3-IO4-Pad26)") (class "Default")
      (node (ref "IC3") (pin "26") (pinfunction "IO4_26") (pintype "bidirectional"))
    )
    (net (code "87") (name "unconnected-(IC3-IO16-Pad27)") (class "Default")
      (node (ref "IC3") (pin "27") (pinfunction "IO16_27") (pintype "bidirectional"))
    )
    (net (code "88") (name "unconnected-(IC3-IO20-Pad32)") (class "Default")
      (node (ref "IC3") (pin "32") (pinfunction "IO20_32") (pintype "bidirectional"))
    )
    (net (code "89") (name "unconnected-(IC3-SENSOR_VN-Pad5)") (class "Default")
      (node (ref "IC3") (pin "5") (pinfunction "SENSOR_VN_5") (pintype "bidirectional"))
    )
    (net (code "90") (name "unconnected-(IC3-SENSOR_VP-Pad4)") (class "Default")
      (node (ref "IC3") (pin "4") (pinfunction "SENSOR_VP_4") (pintype "bidirectional"))
    )
    (net (code "91") (name "unconnected-(IC5-IO2-Pad24)") (class "Default")
      (node (ref "IC5") (pin "24") (pinfunction "IO2_24") (pintype "bidirectional"))
    )
    (net (code "92") (name "unconnected-(IC5-IO4-Pad26)") (class "Default")
      (node (ref "IC5") (pin "26") (pinfunction "IO4_26") (pintype "bidirectional"))
    )
    (net (code "93") (name "unconnected-(IC5-IO16-Pad27)") (class "Default")
      (node (ref "IC5") (pin "27") (pinfunction "IO16_27") (pintype "bidirectional"))
    )
    (net (code "94") (name "unconnected-(IC5-IO20-Pad32)") (class "Default")
      (node (ref "IC5") (pin "32") (pinfunction "IO20_32") (pintype "bidirectional"))
    )
    (net (code "95") (name "unconnected-(IC5-SENSOR_VN-Pad5)") (class "Default")
      (node (ref "IC5") (pin "5") (pinfunction "SENSOR_VN_5") (pintype "bidirectional"))
    )
    (net (code "96") (name "unconnected-(IC5-SENSOR_VP-Pad4)") (class "Default")
      (node (ref "IC5") (pin "4") (pinfunction "SENSOR_VP_4") (pintype "bidirectional"))
    )
    (net (code "97") (name "unconnected-(IC8-ON{slash}OFF-PadP$5)") (class "Default")
      (node (ref "IC8") (pin "P$5") (pinfunction "ON/OFF_P$5") (pintype "bidirectional"))
    )
    (net (code "98") (name "unconnected-(IC8-SCL-PadP$17)") (class "Default")
      (node (ref "IC8") (pin "P$17") (pinfunction "SCL_P$17") (pintype "bidirectional"))
    )
    (net (code "99") (name "unconnected-(IC8-SDA-PadP$16)") (class "Default")
      (node (ref "IC8") (pin "P$16") (pinfunction "SDA_P$16") (pintype "bidirectional"))
    )
    (net (code "100") (name "unconnected-(IC8-VCC_RF-PadP$14)") (class "Default")
      (node (ref "IC8") (pin "P$14") (pinfunction "VCC_RF_P$14") (pintype "bidirectional"))
    )
    (net (code "101") (name "unconnected-(IC10-IO2-Pad24)") (class "Default")
      (node (ref "IC10") (pin "24") (pinfunction "IO2_24") (pintype "bidirectional"))
    )
    (net (code "102") (name "unconnected-(IC10-IO4-Pad26)") (class "Default")
      (node (ref "IC10") (pin "26") (pinfunction "IO4_26") (pintype "bidirectional"))
    )
    (net (code "103") (name "unconnected-(IC10-IO16-Pad27)") (class "Default")
      (node (ref "IC10") (pin "27") (pinfunction "IO16_27") (pintype "bidirectional"))
    )
    (net (code "104") (name "unconnected-(IC10-IO20-Pad32)") (class "Default")
      (node (ref "IC10") (pin "32") (pinfunction "IO20_32") (pintype "bidirectional"))
    )
    (net (code "105") (name "unconnected-(IC10-SENSOR_VN-Pad5)") (class "Default")
      (node (ref "IC10") (pin "5") (pinfunction "SENSOR_VN_5") (pintype "bidirectional"))
    )
    (net (code "106") (name "unconnected-(IC10-SENSOR_VP-Pad4)") (class "Default")
      (node (ref "IC10") (pin "4") (pinfunction "SENSOR_VP_4") (pintype "bidirectional"))
    )
    (net (code "107") (name "unconnected-(IC13-ON{slash}OFF-PadP$5)") (class "Default")
      (node (ref "IC13") (pin "P$5") (pinfunction "ON/OFF_P$5") (pintype "bidirectional"))
    )
    (net (code "108") (name "unconnected-(IC13-SCL-PadP$17)") (class "Default")
      (node (ref "IC13") (pin "P$17") (pinfunction "SCL_P$17") (pintype "bidirectional"))
    )
    (net (code "109") (name "unconnected-(IC13-SDA-PadP$16)") (class "Default")
      (node (ref "IC13") (pin "P$16") (pinfunction "SDA_P$16") (pintype "bidirectional"))
    )
    (net (code "110") (name "unconnected-(IC13-VCC_RF-PadP$14)") (class "Default")
      (node (ref "IC13") (pin "P$14") (pinfunction "VCC_RF_P$14") (pintype "bidirectional"))
    )
    (net (code "111") (name "unconnected-(IC15-IO2-Pad24)") (class "Default")
      (node (ref "IC15") (pin "24") (pinfunction "IO2_24") (pintype "bidirectional"))
    )
    (net (code "112") (name "unconnected-(IC15-IO4-Pad26)") (class "Default")
      (node (ref "IC15") (pin "26") (pinfunction "IO4_26") (pintype "bidirectional"))
    )
    (net (code "113") (name "unconnected-(IC15-IO16-Pad27)") (class "Default")
      (node (ref "IC15") (pin "27") (pinfunction "IO16_27") (pintype "bidirectional"))
    )
    (net (code "114") (name "unconnected-(IC15-IO20-Pad32)") (class "Default")
      (node (ref "IC15") (pin "32") (pinfunction "IO20_32") (pintype "bidirectional"))
    )
    (net (code "115") (name "unconnected-(IC15-SENSOR_VN-Pad5)") (class "Default")
      (node (ref "IC15") (pin "5") (pinfunction "SENSOR_VN_5") (pintype "bidirectional"))
    )
    (net (code "116") (name "unconnected-(IC15-SENSOR_VP-Pad4)") (class "Default")
      (node (ref "IC15") (pin "4") (pinfunction "SENSOR_VP_4") (pintype "bidirectional"))
    )
    (net (code "117") (name "unconnected-(IC18-ON{slash}OFF-PadP$5)") (class "Default")
      (node (ref "IC18") (pin "P$5") (pinfunction "ON/OFF_P$5") (pintype "bidirectional"))
    )
    (net (code "118") (name "unconnected-(IC18-SCL-PadP$17)") (class "Default")
      (node (ref "IC18") (pin "P$17") (pinfunction "SCL_P$17") (pintype "bidirectional"))
    )
    (net (code "119") (name "unconnected-(IC18-SDA-PadP$16)") (class "Default")
      (node (ref "IC18") (pin "P$16") (pinfunction "SDA_P$16") (pintype "bidirectional"))
    )
    (net (code "120") (name "unconnected-(IC18-VCC_RF-PadP$14)") (class "Default")
      (node (ref "IC18") (pin "P$14") (pinfunction "VCC_RF_P$14") (pintype "bidirectional"))
    )
    (net (code "121") (name "unconnected-(IC54-ON{slash}OFF-PadP$5)") (class "Default")
      (node (ref "IC54") (pin "P$5") (pinfunction "ON/OFF_P$5") (pintype "bidirectional"))
    )
    (net (code "122") (name "unconnected-(IC54-SCL-PadP$17)") (class "Default")
      (node (ref "IC54") (pin "P$17") (pinfunction "SCL_P$17") (pintype "bidirectional"))
    )
    (net (code "123") (name "unconnected-(IC54-SDA-PadP$16)") (class "Default")
      (node (ref "IC54") (pin "P$16") (pinfunction "SDA_P$16") (pintype "bidirectional"))
    )
    (net (code "124") (name "unconnected-(IC54-VCC_RF-PadP$14)") (class "Default")
      (node (ref "IC54") (pin "P$14") (pinfunction "VCC_RF_P$14") (pintype "bidirectional"))
    )
    (net (code "125") (name "unconnected-(U1-DIO3-Pad11)") (class "Default")
      (node (ref "U1") (pin "11") (pinfunction "DIO3_11") (pintype "bidirectional"))
    )
    (net (code "126") (name "unconnected-(U1-DIO4-Pad12)") (class "Default")
      (node (ref "U1") (pin "12") (pinfunction "DIO4_12") (pintype "bidirectional"))
    )
    (net (code "127") (name "unconnected-(U2-DIO3-Pad11)") (class "Default")
      (node (ref "U2") (pin "11") (pinfunction "DIO3_11") (pintype "bidirectional"))
    )
    (net (code "128") (name "unconnected-(U2-DIO4-Pad12)") (class "Default")
      (node (ref "U2") (pin "12") (pinfunction "DIO4_12") (pintype "bidirectional"))
    )
    (net (code "129") (name "unconnected-(U3-DIO3-Pad11)") (class "Default")
      (node (ref "U3") (pin "11") (pinfunction "DIO3_11") (pintype "bidirectional"))
    )
    (net (code "130") (name "unconnected-(U3-DIO4-Pad12)") (class "Default")
      (node (ref "U3") (pin "12") (pinfunction "DIO4_12") (pintype "bidirectional"))
    )
    (net (code "131") (name "unconnected-(U4-DIO3-Pad11)") (class "Default")
      (node (ref "U4") (pin "11") (pinfunction "DIO3_11") (pintype "bidirectional"))
    )
    (net (code "132") (name "unconnected-(U4-DIO4-Pad12)") (class "Default")
      (node (ref "U4") (pin "12") (pinfunction "DIO4_12") (pintype "bidirectional"))
    )
  )
)
